# HSI-interface-1.net
KiCad netlist of a schematic drawn in EAGLE
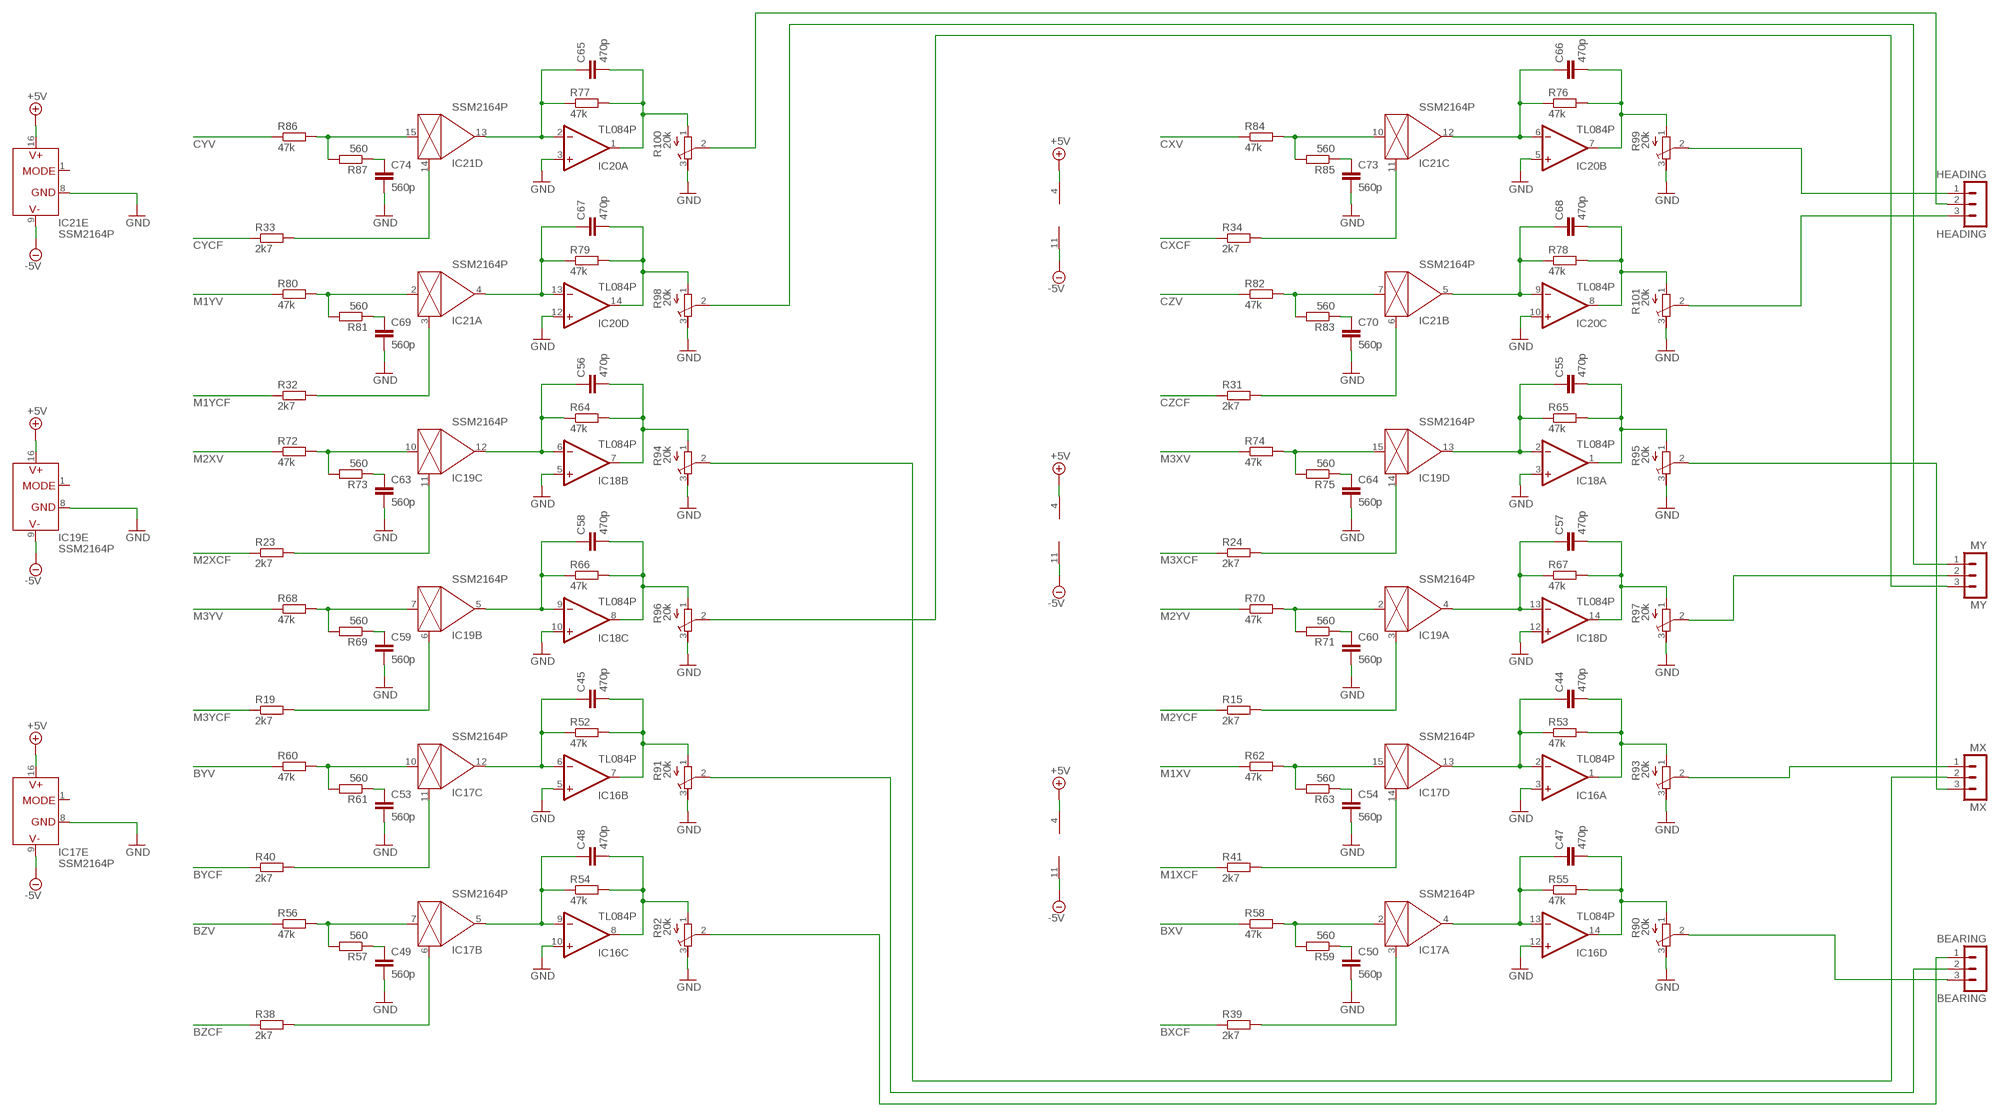
[diagram p0: schematic, sheet 1]
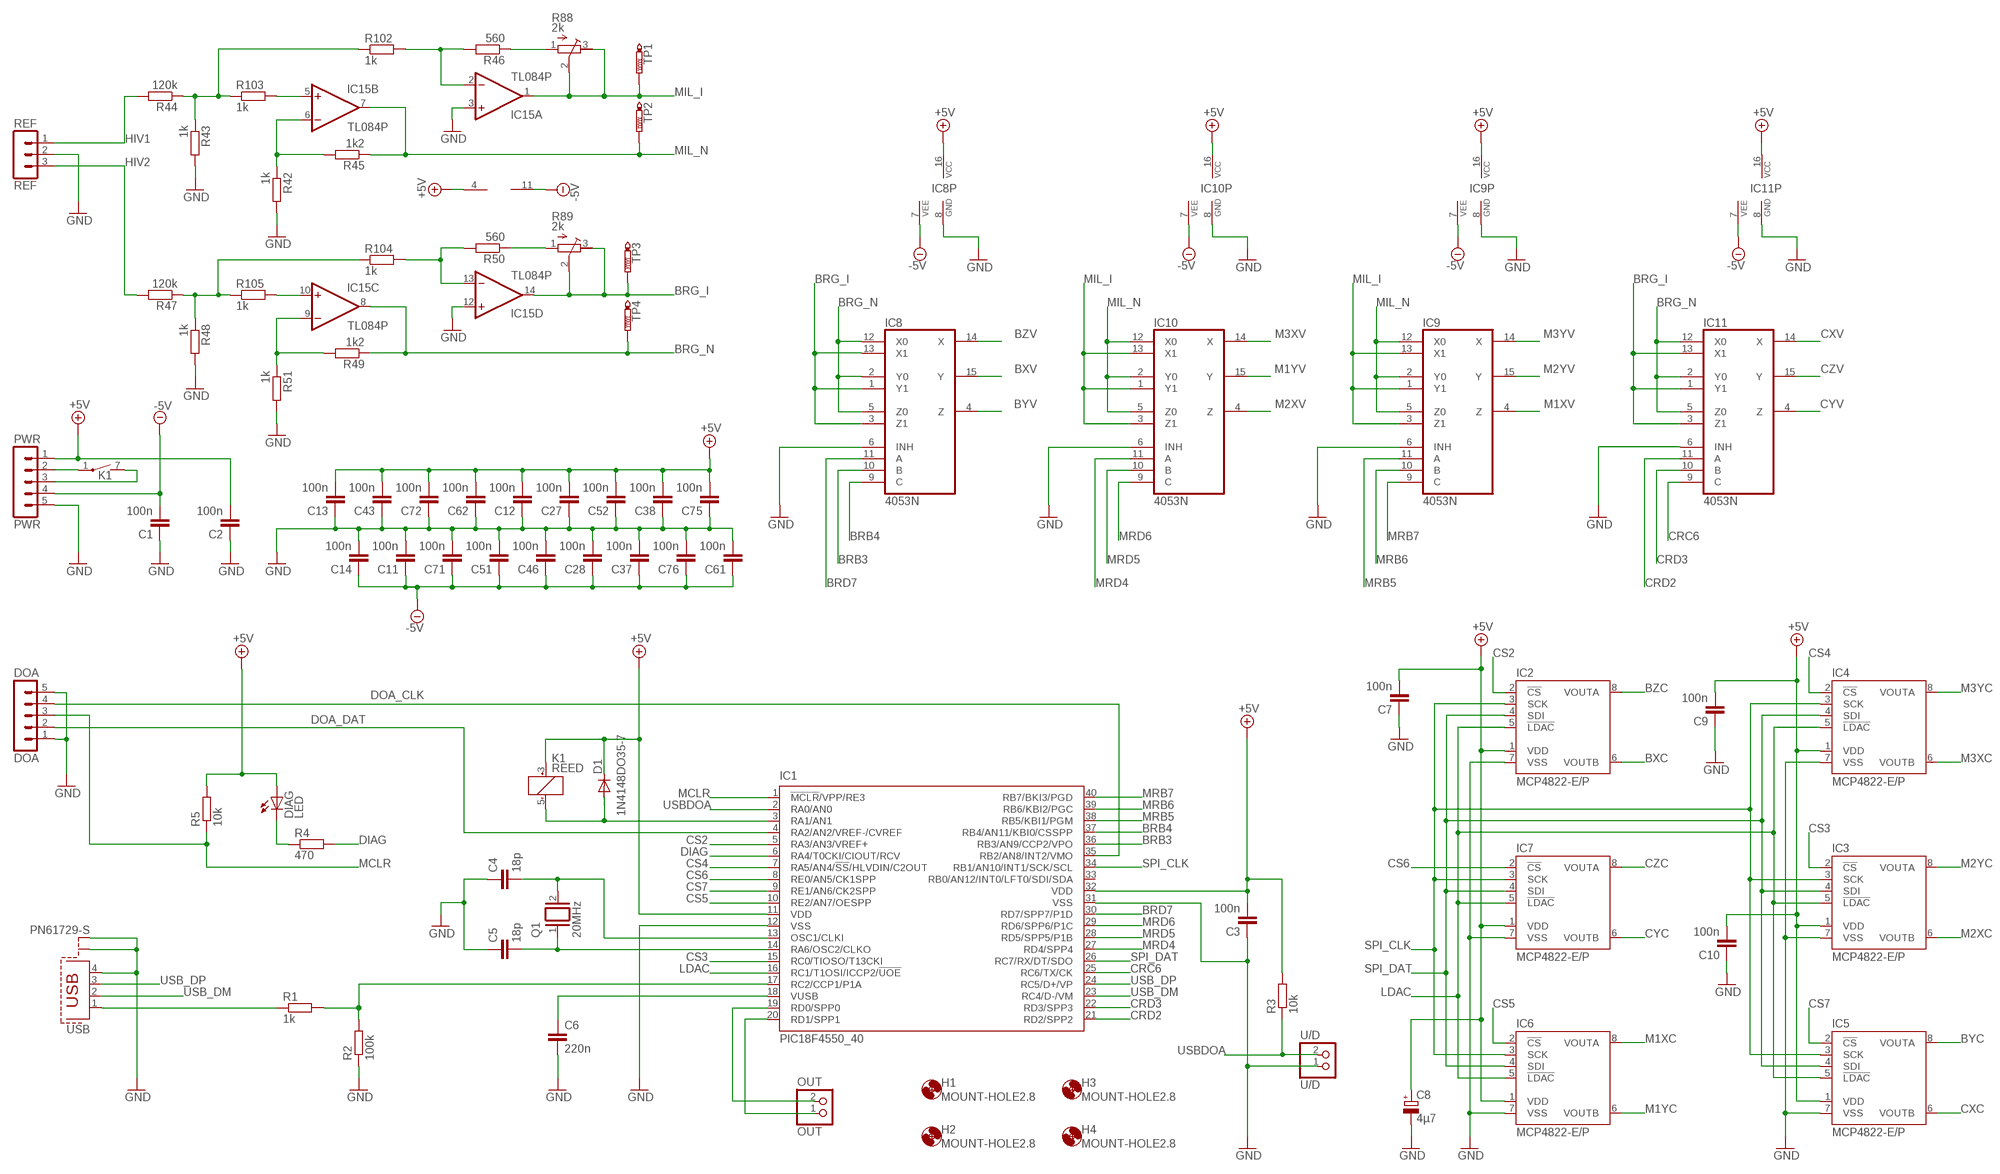
[diagram p1: schematic, sheet 2]
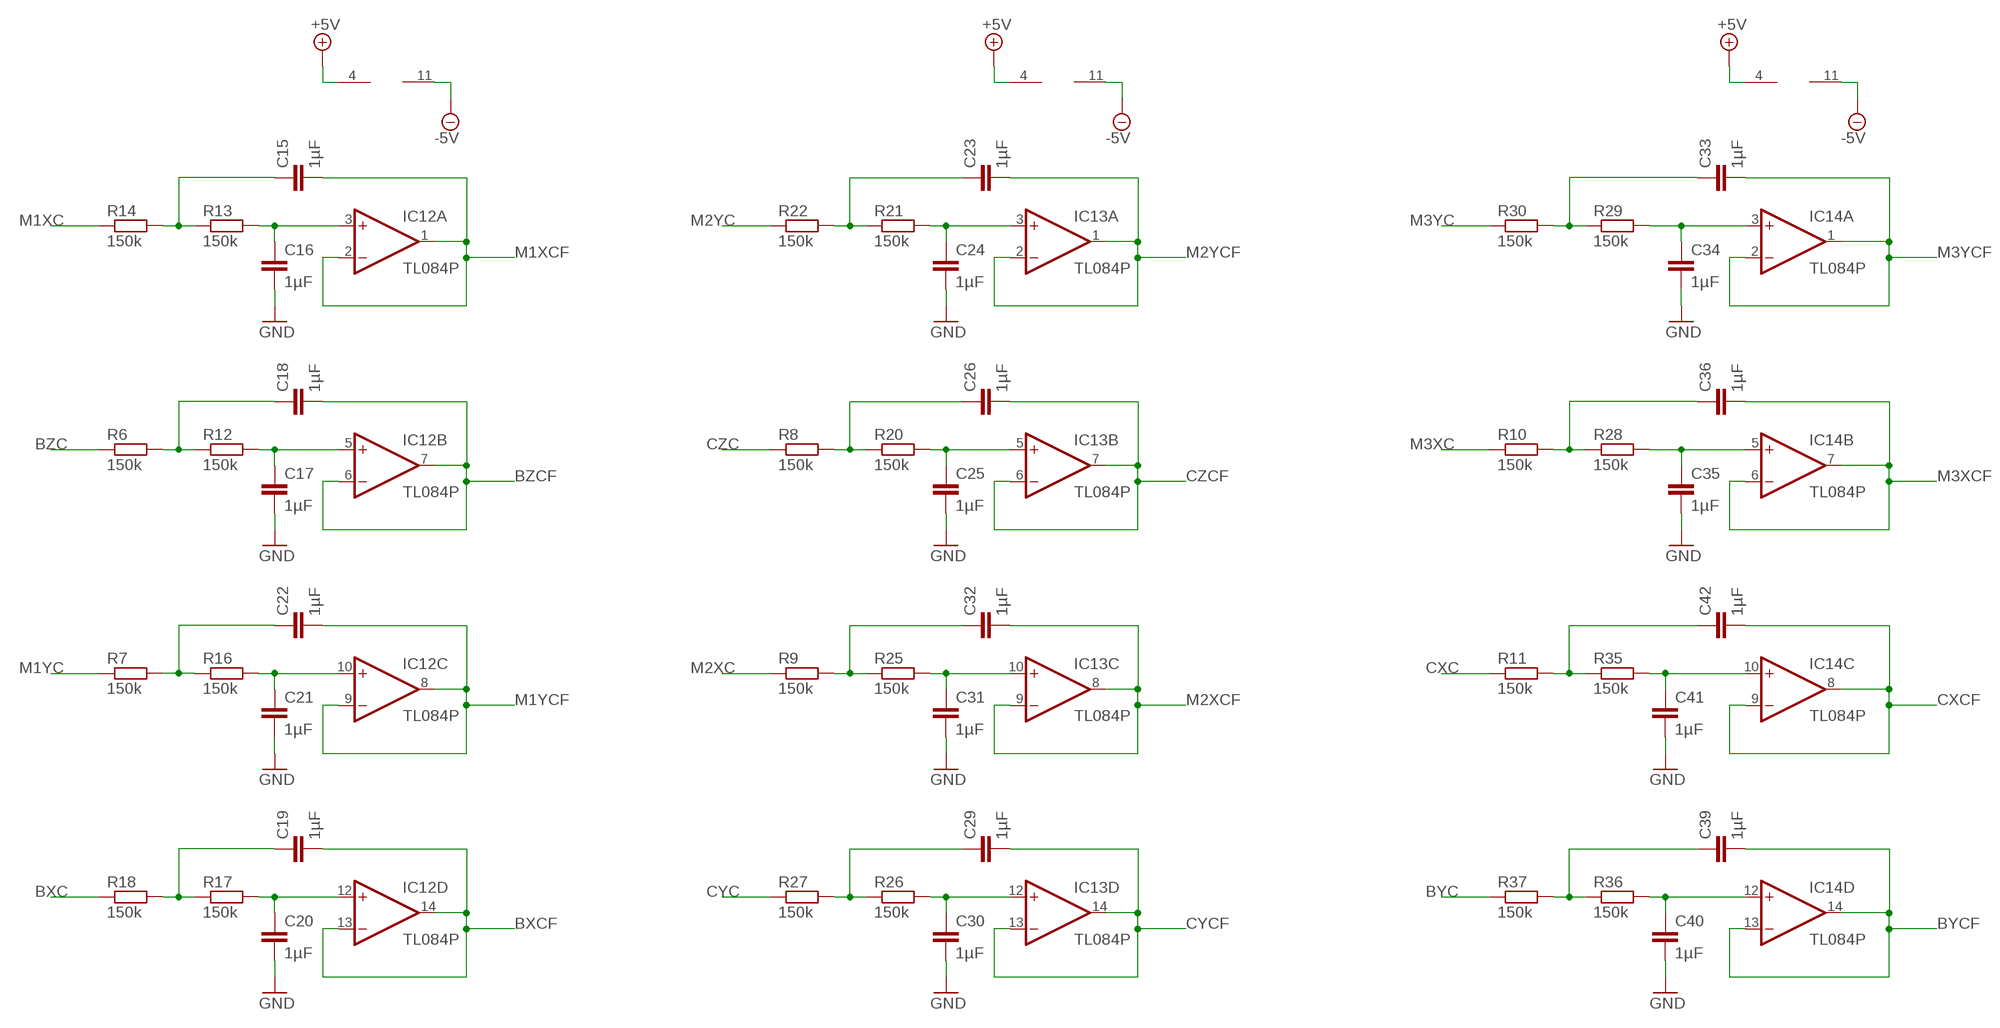
[diagram p2: schematic, sheet 3]

(export (version "E")
  (design (tool "Eeschema 10.0.6"))
  (components
    (comp (ref "C15")
      (value "1µF")
      (footprint "eagle-import:C025-025X050")
      (libsource (lib "eagle-import") (part "C-EU025-025X050"))
    )
    (comp (ref "C16")
      (value "1µF")
      (footprint "eagle-import:C025-025X050")
      (libsource (lib "eagle-import") (part "C-EU025-025X050"))
    )
    (comp (ref "C17")
      (value "1µF")
      (footprint "eagle-import:C025-025X050")
      (libsource (lib "eagle-import") (part "C-EU025-025X050"))
    )
    (comp (ref "C18")
      (value "1µF")
      (footprint "eagle-import:C025-025X050")
      (libsource (lib "eagle-import") (part "C-EU025-025X050"))
    )
    (comp (ref "C19")
      (value "1µF")
      (footprint "eagle-import:C025-025X050")
      (libsource (lib "eagle-import") (part "C-EU025-025X050"))
    )
    (comp (ref "C20")
      (value "1µF")
      (footprint "eagle-import:C025-025X050")
      (libsource (lib "eagle-import") (part "C-EU025-025X050"))
    )
    (comp (ref "C21")
      (value "1µF")
      (footprint "eagle-import:C025-025X050")
      (libsource (lib "eagle-import") (part "C-EU025-025X050"))
    )
    (comp (ref "C22")
      (value "1µF")
      (footprint "eagle-import:C025-025X050")
      (libsource (lib "eagle-import") (part "C-EU025-025X050"))
    )
    (comp (ref "C23")
      (value "1µF")
      (footprint "eagle-import:C025-025X050")
      (libsource (lib "eagle-import") (part "C-EU025-025X050"))
    )
    (comp (ref "C24")
      (value "1µF")
      (footprint "eagle-import:C025-025X050")
      (libsource (lib "eagle-import") (part "C-EU025-025X050"))
    )
    (comp (ref "C25")
      (value "1µF")
      (footprint "eagle-import:C025-025X050")
      (libsource (lib "eagle-import") (part "C-EU025-025X050"))
    )
    (comp (ref "C26")
      (value "1µF")
      (footprint "eagle-import:C025-025X050")
      (libsource (lib "eagle-import") (part "C-EU025-025X050"))
    )
    (comp (ref "C29")
      (value "1µF")
      (footprint "eagle-import:C025-025X050")
      (libsource (lib "eagle-import") (part "C-EU025-025X050"))
    )
    (comp (ref "C30")
      (value "1µF")
      (footprint "eagle-import:C025-025X050")
      (libsource (lib "eagle-import") (part "C-EU025-025X050"))
    )
    (comp (ref "C31")
      (value "1µF")
      (footprint "eagle-import:C025-025X050")
      (libsource (lib "eagle-import") (part "C-EU025-025X050"))
    )
    (comp (ref "C32")
      (value "1µF")
      (footprint "eagle-import:C025-025X050")
      (libsource (lib "eagle-import") (part "C-EU025-025X050"))
    )
    (comp (ref "C33")
      (value "1µF")
      (footprint "eagle-import:C025-025X050")
      (libsource (lib "eagle-import") (part "C-EU025-025X050"))
    )
    (comp (ref "C34")
      (value "1µF")
      (footprint "eagle-import:C025-025X050")
      (libsource (lib "eagle-import") (part "C-EU025-025X050"))
    )
    (comp (ref "C35")
      (value "1µF")
      (footprint "eagle-import:C025-025X050")
      (libsource (lib "eagle-import") (part "C-EU025-025X050"))
    )
    (comp (ref "C36")
      (value "1µF")
      (footprint "eagle-import:C025-025X050")
      (libsource (lib "eagle-import") (part "C-EU025-025X050"))
    )
    (comp (ref "C39")
      (value "1µF")
      (footprint "eagle-import:C025-025X050")
      (libsource (lib "eagle-import") (part "C-EU025-025X050"))
    )
    (comp (ref "C40")
      (value "1µF")
      (footprint "eagle-import:C025-025X050")
      (libsource (lib "eagle-import") (part "C-EU025-025X050"))
    )
    (comp (ref "C41")
      (value "1µF")
      (footprint "eagle-import:C025-025X050")
      (libsource (lib "eagle-import") (part "C-EU025-025X050"))
    )
    (comp (ref "C42")
      (value "1µF")
      (footprint "eagle-import:C025-025X050")
      (libsource (lib "eagle-import") (part "C-EU025-025X050"))
    )
    (comp (ref "IC12")
      (value "TL084P")
      (footprint "eagle-import:DIL14")
      (libsource (lib "eagle-import") (part "TL084P"))
    )
    (comp (ref "IC13")
      (value "TL084P")
      (footprint "eagle-import:DIL14")
      (libsource (lib "eagle-import") (part "TL084P"))
    )
    (comp (ref "IC14")
      (value "TL084P")
      (footprint "eagle-import:DIL14")
      (libsource (lib "eagle-import") (part "TL084P"))
    )
    (comp (ref "R6")
      (value "150k")
      (footprint "eagle-import:0207_7")
      (libsource (lib "eagle-import") (part "R-EU_0207/7"))
    )
    (comp (ref "R7")
      (value "150k")
      (footprint "eagle-import:0207_7")
      (libsource (lib "eagle-import") (part "R-EU_0207/7"))
    )
    (comp (ref "R8")
      (value "150k")
      (footprint "eagle-import:0207_7")
      (libsource (lib "eagle-import") (part "R-EU_0207/7"))
    )
    (comp (ref "R9")
      (value "150k")
      (footprint "eagle-import:0207_7")
      (libsource (lib "eagle-import") (part "R-EU_0207/7"))
    )
    (comp (ref "R10")
      (value "150k")
      (footprint "eagle-import:0207_7")
      (libsource (lib "eagle-import") (part "R-EU_0207/7"))
    )
    (comp (ref "R11")
      (value "150k")
      (footprint "eagle-import:0207_7")
      (libsource (lib "eagle-import") (part "R-EU_0207/7"))
    )
    (comp (ref "R12")
      (value "150k")
      (footprint "eagle-import:0207_7")
      (libsource (lib "eagle-import") (part "R-EU_0207/7"))
    )
    (comp (ref "R13")
      (value "150k")
      (footprint "eagle-import:0207_7")
      (libsource (lib "eagle-import") (part "R-EU_0207/7"))
    )
    (comp (ref "R14")
      (value "150k")
      (footprint "eagle-import:0207_7")
      (libsource (lib "eagle-import") (part "R-EU_0207/7"))
    )
    (comp (ref "R16")
      (value "150k")
      (footprint "eagle-import:0207_7")
      (libsource (lib "eagle-import") (part "R-EU_0207/7"))
    )
    (comp (ref "R17")
      (value "150k")
      (footprint "eagle-import:0207_7")
      (libsource (lib "eagle-import") (part "R-EU_0207/7"))
    )
    (comp (ref "R18")
      (value "150k")
      (footprint "eagle-import:0207_7")
      (libsource (lib "eagle-import") (part "R-EU_0207/7"))
    )
    (comp (ref "R20")
      (value "150k")
      (footprint "eagle-import:0207_7")
      (libsource (lib "eagle-import") (part "R-EU_0207/7"))
    )
    (comp (ref "R21")
      (value "150k")
      (footprint "eagle-import:0207_7")
      (libsource (lib "eagle-import") (part "R-EU_0207/7"))
    )
    (comp (ref "R22")
      (value "150k")
      (footprint "eagle-import:0207_7")
      (libsource (lib "eagle-import") (part "R-EU_0207/7"))
    )
    (comp (ref "R25")
      (value "150k")
      (footprint "eagle-import:0207_7")
      (libsource (lib "eagle-import") (part "R-EU_0207/7"))
    )
    (comp (ref "R26")
      (value "150k")
      (footprint "eagle-import:0207_7")
      (libsource (lib "eagle-import") (part "R-EU_0207/7"))
    )
    (comp (ref "R27")
      (value "150k")
      (footprint "eagle-import:0207_7")
      (libsource (lib "eagle-import") (part "R-EU_0207/7"))
    )
    (comp (ref "R28")
      (value "150k")
      (footprint "eagle-import:0207_7")
      (libsource (lib "eagle-import") (part "R-EU_0207/7"))
    )
    (comp (ref "R29")
      (value "150k")
      (footprint "eagle-import:0207_7")
      (libsource (lib "eagle-import") (part "R-EU_0207/7"))
    )
    (comp (ref "R30")
      (value "150k")
      (footprint "eagle-import:0207_7")
      (libsource (lib "eagle-import") (part "R-EU_0207/7"))
    )
    (comp (ref "R35")
      (value "150k")
      (footprint "eagle-import:0207_7")
      (libsource (lib "eagle-import") (part "R-EU_0207/7"))
    )
    (comp (ref "R36")
      (value "150k")
      (footprint "eagle-import:0207_7")
      (libsource (lib "eagle-import") (part "R-EU_0207/7"))
    )
    (comp (ref "R37")
      (value "150k")
      (footprint "eagle-import:0207_7")
      (libsource (lib "eagle-import") (part "R-EU_0207/7"))
    )
    (comp (ref "C1")
      (value "100n")
      (footprint "eagle-import:C025-025X050")
      (libsource (lib "eagle-import") (part "C-EU025-025X050"))
    )
    (comp (ref "C2")
      (value "100n")
      (footprint "eagle-import:C025-025X050")
      (libsource (lib "eagle-import") (part "C-EU025-025X050"))
    )
    (comp (ref "C3")
      (value "100n")
      (footprint "eagle-import:C025-025X050")
      (libsource (lib "eagle-import") (part "C-EU025-025X050"))
    )
    (comp (ref "C4")
      (value "18p")
      (footprint "eagle-import:C025-025X050")
      (libsource (lib "eagle-import") (part "C-EU025-025X050"))
    )
    (comp (ref "C5")
      (value "18p")
      (footprint "eagle-import:C025-025X050")
      (libsource (lib "eagle-import") (part "C-EU025-025X050"))
    )
    (comp (ref "C6")
      (value "220n")
      (footprint "eagle-import:C5B3")
      (libsource (lib "eagle-import") (part "C5/3"))
    )
    (comp (ref "C7")
      (value "100n")
      (footprint "eagle-import:C025-025X050")
      (libsource (lib "eagle-import") (part "C-EU025-025X050"))
    )
    (comp (ref "C8")
      (value "4µ7")
      (footprint "eagle-import:E2,5-5")
      (libsource (lib "eagle-import") (part "CPOL-EUE2.5-5"))
    )
    (comp (ref "C9")
      (value "100n")
      (footprint "eagle-import:C025-025X050")
      (libsource (lib "eagle-import") (part "C-EU025-025X050"))
    )
    (comp (ref "C10")
      (value "100n")
      (footprint "eagle-import:C025-025X050")
      (libsource (lib "eagle-import") (part "C-EU025-025X050"))
    )
    (comp (ref "C11")
      (value "100n")
      (footprint "eagle-import:C025-025X050")
      (libsource (lib "eagle-import") (part "C-EU025-025X050"))
    )
    (comp (ref "C12")
      (value "100n")
      (footprint "eagle-import:C025-025X050")
      (libsource (lib "eagle-import") (part "C-EU025-025X050"))
    )
    (comp (ref "C13")
      (value "100n")
      (footprint "eagle-import:C025-025X050")
      (libsource (lib "eagle-import") (part "C-EU025-025X050"))
    )
    (comp (ref "C14")
      (value "100n")
      (footprint "eagle-import:C025-025X050")
      (libsource (lib "eagle-import") (part "C-EU025-025X050"))
    )
    (comp (ref "C27")
      (value "100n")
      (footprint "eagle-import:C025-025X050")
      (libsource (lib "eagle-import") (part "C-EU025-025X050"))
    )
    (comp (ref "C28")
      (value "100n")
      (footprint "eagle-import:C025-025X050")
      (libsource (lib "eagle-import") (part "C-EU025-025X050"))
    )
    (comp (ref "C37")
      (value "100n")
      (footprint "eagle-import:C025-025X050")
      (libsource (lib "eagle-import") (part "C-EU025-025X050"))
    )
    (comp (ref "C38")
      (value "100n")
      (footprint "eagle-import:C025-025X050")
      (libsource (lib "eagle-import") (part "C-EU025-025X050"))
    )
    (comp (ref "C43")
      (value "100n")
      (footprint "eagle-import:C025-025X050")
      (libsource (lib "eagle-import") (part "C-EU025-025X050"))
    )
    (comp (ref "C46")
      (value "100n")
      (footprint "eagle-import:C025-025X050")
      (libsource (lib "eagle-import") (part "C-EU025-025X050"))
    )
    (comp (ref "C51")
      (value "100n")
      (footprint "eagle-import:C025-025X050")
      (libsource (lib "eagle-import") (part "C-EU025-025X050"))
    )
    (comp (ref "C52")
      (value "100n")
      (footprint "eagle-import:C025-025X050")
      (libsource (lib "eagle-import") (part "C-EU025-025X050"))
    )
    (comp (ref "C61")
      (value "100n")
      (footprint "eagle-import:C025-025X050")
      (libsource (lib "eagle-import") (part "C-EU025-025X050"))
    )
    (comp (ref "C62")
      (value "100n")
      (footprint "eagle-import:C025-025X050")
      (libsource (lib "eagle-import") (part "C-EU025-025X050"))
    )
    (comp (ref "C71")
      (value "100n")
      (footprint "eagle-import:C025-025X050")
      (libsource (lib "eagle-import") (part "C-EU025-025X050"))
    )
    (comp (ref "C72")
      (value "100n")
      (footprint "eagle-import:C025-025X050")
      (libsource (lib "eagle-import") (part "C-EU025-025X050"))
    )
    (comp (ref "C75")
      (value "100n")
      (footprint "eagle-import:C025-025X050")
      (libsource (lib "eagle-import") (part "C-EU025-025X050"))
    )
    (comp (ref "C76")
      (value "100n")
      (footprint "eagle-import:C025-025X050")
      (libsource (lib "eagle-import") (part "C-EU025-025X050"))
    )
    (comp (ref "D1")
      (value "1N4148DO35-7")
      (footprint "eagle-import:DO35-7")
      (libsource (lib "eagle-import") (part "1N4148DO35-7"))
    )
    (comp (ref "DIAG")
      (value "LED")
      (footprint "eagle-import:LED3MM")
      (libsource (lib "eagle-import") (part "LED3MM"))
    )
    (comp (ref "DOA")
      (value "DOA")
      (footprint "eagle-import:MA05-1")
      (libsource (lib "eagle-import") (part "MA05-1"))
    )
    (comp (ref "H1")
      (value "MOUNT-HOLE2.8")
      (footprint "eagle-import:2,8")
      (libsource (lib "eagle-import") (part "MOUNT-HOLE2.8"))
    )
    (comp (ref "H2")
      (value "MOUNT-HOLE2.8")
      (footprint "eagle-import:2,8")
      (libsource (lib "eagle-import") (part "MOUNT-HOLE2.8"))
    )
    (comp (ref "H3")
      (value "MOUNT-HOLE2.8")
      (footprint "eagle-import:2,8")
      (libsource (lib "eagle-import") (part "MOUNT-HOLE2.8"))
    )
    (comp (ref "H4")
      (value "MOUNT-HOLE2.8")
      (footprint "eagle-import:2,8")
      (libsource (lib "eagle-import") (part "MOUNT-HOLE2.8"))
    )
    (comp (ref "IC1")
      (value "PIC18F4550_40")
      (footprint "eagle-import:DIL40")
      (fields (field (name "MF") "MICROCHIP") (field (name "MPN") "PIC18F4550-I/P"))
      (libsource (lib "eagle-import") (part "PIC18F4_40550"))
    )
    (comp (ref "IC2")
      (value "MCP4822-E/P")
      (footprint "eagle-import:DIL08")
      (libsource (lib "eagle-import") (part "MCP4822-E/P"))
    )
    (comp (ref "IC3")
      (value "MCP4822-E/P")
      (footprint "eagle-import:DIL08")
      (libsource (lib "eagle-import") (part "MCP4822-E/P"))
    )
    (comp (ref "IC4")
      (value "MCP4822-E/P")
      (footprint "eagle-import:DIL08")
      (libsource (lib "eagle-import") (part "MCP4822-E/P"))
    )
    (comp (ref "IC5")
      (value "MCP4822-E/P")
      (footprint "eagle-import:DIL08")
      (libsource (lib "eagle-import") (part "MCP4822-E/P"))
    )
    (comp (ref "IC6")
      (value "MCP4822-E/P")
      (footprint "eagle-import:DIL08")
      (libsource (lib "eagle-import") (part "MCP4822-E/P"))
    )
    (comp (ref "IC7")
      (value "MCP4822-E/P")
      (footprint "eagle-import:DIL08")
      (libsource (lib "eagle-import") (part "MCP4822-E/P"))
    )
    (comp (ref "IC8")
      (value "4053N")
      (footprint "eagle-import:DIL16")
      (libsource (lib "eagle-import") (part "4053N"))
    )
    (comp (ref "IC9")
      (value "4053N")
      (footprint "eagle-import:DIL16")
      (libsource (lib "eagle-import") (part "4053N"))
    )
    (comp (ref "IC10")
      (value "4053N")
      (footprint "eagle-import:DIL16")
      (libsource (lib "eagle-import") (part "4053N"))
    )
    (comp (ref "IC11")
      (value "4053N")
      (footprint "eagle-import:DIL16")
      (libsource (lib "eagle-import") (part "4053N"))
    )
    (comp (ref "IC15")
      (value "TL084P")
      (footprint "eagle-import:DIL14")
      (libsource (lib "eagle-import") (part "TL084P"))
    )
    (comp (ref "K1")
      (value "REED")
      (footprint "eagle-import:REED")
      (libsource (lib "eagle-import") (part "REED"))
    )
    (comp (ref "OUT")
      (value "OUT")
      (footprint "eagle-import:1X02")
      (libsource (lib "eagle-import") (part "PINHD-1X2"))
    )
    (comp (ref "PWR")
      (value "PWR")
      (footprint "eagle-import:MA05-1")
      (libsource (lib "eagle-import") (part "MA05-1"))
    )
    (comp (ref "Q1")
      (value "20MHz")
      (footprint "eagle-import:QS")
      (libsource (lib "eagle-import") (part "XTAL/S"))
    )
    (comp (ref "R1")
      (value "1k")
      (footprint "eagle-import:0204_7")
      (libsource (lib "eagle-import") (part "R-EU_0204/7"))
    )
    (comp (ref "R2")
      (value "100k")
      (footprint "eagle-import:0204_7")
      (libsource (lib "eagle-import") (part "R-EU_0204/7"))
    )
    (comp (ref "R3")
      (value "10k")
      (footprint "eagle-import:0204_7")
      (libsource (lib "eagle-import") (part "R-EU_0204/7"))
    )
    (comp (ref "R4")
      (value "470")
      (footprint "eagle-import:0204_7")
      (libsource (lib "eagle-import") (part "R-EU_0204/7"))
    )
    (comp (ref "R5")
      (value "10k")
      (footprint "eagle-import:0204_7")
      (libsource (lib "eagle-import") (part "R-EU_0204/7"))
    )
    (comp (ref "R42")
      (value "1k")
      (footprint "eagle-import:0204_7")
      (libsource (lib "eagle-import") (part "R-EU_0204/7"))
    )
    (comp (ref "R43")
      (value "1k")
      (footprint "eagle-import:0204_7")
      (libsource (lib "eagle-import") (part "R-EU_0204/7"))
    )
    (comp (ref "R44")
      (value "120k")
      (footprint "eagle-import:0204_7")
      (libsource (lib "eagle-import") (part "R-EU_0204/7"))
    )
    (comp (ref "R45")
      (value "1k2")
      (footprint "eagle-import:0204_7")
      (libsource (lib "eagle-import") (part "R-EU_0204/7"))
    )
    (comp (ref "R46")
      (value "560")
      (footprint "eagle-import:0204_7")
      (libsource (lib "eagle-import") (part "R-EU_0204/7"))
    )
    (comp (ref "R47")
      (value "120k")
      (footprint "eagle-import:0204_7")
      (libsource (lib "eagle-import") (part "R-EU_0204/7"))
    )
    (comp (ref "R48")
      (value "1k")
      (footprint "eagle-import:0204_7")
      (libsource (lib "eagle-import") (part "R-EU_0204/7"))
    )
    (comp (ref "R49")
      (value "1k2")
      (footprint "eagle-import:0204_7")
      (libsource (lib "eagle-import") (part "R-EU_0204/7"))
    )
    (comp (ref "R50")
      (value "560")
      (footprint "eagle-import:0204_7")
      (libsource (lib "eagle-import") (part "R-EU_0204/7"))
    )
    (comp (ref "R51")
      (value "1k")
      (footprint "eagle-import:0204_7")
      (libsource (lib "eagle-import") (part "R-EU_0204/7"))
    )
    (comp (ref "R88")
      (value "2k")
      (footprint "eagle-import:RTRIM64Z")
      (libsource (lib "eagle-import") (part "R-TRIMM64Z"))
    )
    (comp (ref "R89")
      (value "2k")
      (footprint "eagle-import:RTRIM64Z")
      (libsource (lib "eagle-import") (part "R-TRIMM64Z"))
    )
    (comp (ref "R102")
      (value "1k")
      (footprint "eagle-import:0204_7")
      (libsource (lib "eagle-import") (part "R-EU_0204/7"))
    )
    (comp (ref "R103")
      (value "1k")
      (footprint "eagle-import:0204_7")
      (libsource (lib "eagle-import") (part "R-EU_0204/7"))
    )
    (comp (ref "R104")
      (value "1k")
      (footprint "eagle-import:0204_7")
      (libsource (lib "eagle-import") (part "R-EU_0204/7"))
    )
    (comp (ref "R105")
      (value "1k")
      (footprint "eagle-import:0204_7")
      (libsource (lib "eagle-import") (part "R-EU_0204/7"))
    )
    (comp (ref "REF")
      (value "REF")
      (footprint "eagle-import:MA03-1")
      (libsource (lib "eagle-import") (part "MA03-1"))
    )
    (comp (ref "TP1")
      (value "PTR1PAD1-13")
      (footprint "eagle-import:P1-13")
      (libsource (lib "eagle-import") (part "PTR1PAD1-13"))
    )
    (comp (ref "TP2")
      (value "PTR1PAD1-13")
      (footprint "eagle-import:P1-13")
      (libsource (lib "eagle-import") (part "PTR1PAD1-13"))
    )
    (comp (ref "TP3")
      (value "PTR1PAD1-13")
      (footprint "eagle-import:P1-13")
      (libsource (lib "eagle-import") (part "PTR1PAD1-13"))
    )
    (comp (ref "TP4")
      (value "PTR1PAD1-13")
      (footprint "eagle-import:P1-13")
      (libsource (lib "eagle-import") (part "PTR1PAD1-13"))
    )
    (comp (ref "U/D")
      (value "U/D")
      (footprint "eagle-import:1X02")
      (libsource (lib "eagle-import") (part "PINHD-1X2"))
    )
    (comp (ref "USB")
      (value "PN61729-S")
      (footprint "eagle-import:PN61729-S")
      (libsource (lib "eagle-import") (part "PN61729-S"))
    )
    (comp (ref "BEARING")
      (value "BEARING")
      (footprint "eagle-import:MA03-1")
      (libsource (lib "eagle-import") (part "MA03-1"))
    )
    (comp (ref "C44")
      (value "470p")
      (footprint "eagle-import:C025-025X050")
      (libsource (lib "eagle-import") (part "C-EU025-025X050"))
    )
    (comp (ref "C45")
      (value "470p")
      (footprint "eagle-import:C025-025X050")
      (libsource (lib "eagle-import") (part "C-EU025-025X050"))
    )
    (comp (ref "C47")
      (value "470p")
      (footprint "eagle-import:C025-025X050")
      (libsource (lib "eagle-import") (part "C-EU025-025X050"))
    )
    (comp (ref "C48")
      (value "470p")
      (footprint "eagle-import:C025-025X050")
      (libsource (lib "eagle-import") (part "C-EU025-025X050"))
    )
    (comp (ref "C49")
      (value "560p")
      (footprint "eagle-import:C025-025X050")
      (libsource (lib "eagle-import") (part "C-EU025-025X050"))
    )
    (comp (ref "C50")
      (value "560p")
      (footprint "eagle-import:C025-025X050")
      (libsource (lib "eagle-import") (part "C-EU025-025X050"))
    )
    (comp (ref "C53")
      (value "560p")
      (footprint "eagle-import:C025-025X050")
      (libsource (lib "eagle-import") (part "C-EU025-025X050"))
    )
    (comp (ref "C54")
      (value "560p")
      (footprint "eagle-import:C025-025X050")
      (libsource (lib "eagle-import") (part "C-EU025-025X050"))
    )
    (comp (ref "C55")
      (value "470p")
      (footprint "eagle-import:C025-025X050")
      (libsource (lib "eagle-import") (part "C-EU025-025X050"))
    )
    (comp (ref "C56")
      (value "470p")
      (footprint "eagle-import:C025-025X050")
      (libsource (lib "eagle-import") (part "C-EU025-025X050"))
    )
    (comp (ref "C57")
      (value "470p")
      (footprint "eagle-import:C025-025X050")
      (libsource (lib "eagle-import") (part "C-EU025-025X050"))
    )
    (comp (ref "C58")
      (value "470p")
      (footprint "eagle-import:C025-025X050")
      (libsource (lib "eagle-import") (part "C-EU025-025X050"))
    )
    (comp (ref "C59")
      (value "560p")
      (footprint "eagle-import:C025-025X050")
      (libsource (lib "eagle-import") (part "C-EU025-025X050"))
    )
    (comp (ref "C60")
      (value "560p")
      (footprint "eagle-import:C025-025X050")
      (libsource (lib "eagle-import") (part "C-EU025-025X050"))
    )
    (comp (ref "C63")
      (value "560p")
      (footprint "eagle-import:C025-025X050")
      (libsource (lib "eagle-import") (part "C-EU025-025X050"))
    )
    (comp (ref "C64")
      (value "560p")
      (footprint "eagle-import:C025-025X050")
      (libsource (lib "eagle-import") (part "C-EU025-025X050"))
    )
    (comp (ref "C65")
      (value "470p")
      (footprint "eagle-import:C025-025X050")
      (libsource (lib "eagle-import") (part "C-EU025-025X050"))
    )
    (comp (ref "C66")
      (value "470p")
      (footprint "eagle-import:C025-025X050")
      (libsource (lib "eagle-import") (part "C-EU025-025X050"))
    )
    (comp (ref "C67")
      (value "470p")
      (footprint "eagle-import:C025-025X050")
      (libsource (lib "eagle-import") (part "C-EU025-025X050"))
    )
    (comp (ref "C68")
      (value "470p")
      (footprint "eagle-import:C025-025X050")
      (libsource (lib "eagle-import") (part "C-EU025-025X050"))
    )
    (comp (ref "C69")
      (value "560p")
      (footprint "eagle-import:C025-025X050")
      (libsource (lib "eagle-import") (part "C-EU025-025X050"))
    )
    (comp (ref "C70")
      (value "560p")
      (footprint "eagle-import:C025-025X050")
      (libsource (lib "eagle-import") (part "C-EU025-025X050"))
    )
    (comp (ref "C73")
      (value "560p")
      (footprint "eagle-import:C025-025X050")
      (libsource (lib "eagle-import") (part "C-EU025-025X050"))
    )
    (comp (ref "C74")
      (value "560p")
      (footprint "eagle-import:C025-025X050")
      (libsource (lib "eagle-import") (part "C-EU025-025X050"))
    )
    (comp (ref "HEADING")
      (value "HEADING")
      (footprint "eagle-import:MA03-1")
      (libsource (lib "eagle-import") (part "MA03-1"))
    )
    (comp (ref "IC16")
      (value "TL084P")
      (footprint "eagle-import:DIL14")
      (libsource (lib "eagle-import") (part "TL084P"))
    )
    (comp (ref "IC17")
      (value "SSM2164P")
      (footprint "eagle-import:DIL16")
      (libsource (lib "eagle-import") (part "SSM2164P"))
    )
    (comp (ref "IC18")
      (value "TL084P")
      (footprint "eagle-import:DIL14")
      (libsource (lib "eagle-import") (part "TL084P"))
    )
    (comp (ref "IC19")
      (value "SSM2164P")
      (footprint "eagle-import:DIL16")
      (libsource (lib "eagle-import") (part "SSM2164P"))
    )
    (comp (ref "IC20")
      (value "TL084P")
      (footprint "eagle-import:DIL14")
      (libsource (lib "eagle-import") (part "TL084P"))
    )
    (comp (ref "IC21")
      (value "SSM2164P")
      (footprint "eagle-import:DIL16")
      (libsource (lib "eagle-import") (part "SSM2164P"))
    )
    (comp (ref "MX")
      (value "MX")
      (footprint "eagle-import:MA03-1")
      (libsource (lib "eagle-import") (part "MA03-1"))
    )
    (comp (ref "MY")
      (value "MY")
      (footprint "eagle-import:MA03-1")
      (libsource (lib "eagle-import") (part "MA03-1"))
    )
    (comp (ref "R15")
      (value "2k7")
      (footprint "eagle-import:0207_7")
      (libsource (lib "eagle-import") (part "R-EU_0207/7"))
    )
    (comp (ref "R19")
      (value "2k7")
      (footprint "eagle-import:0207_7")
      (libsource (lib "eagle-import") (part "R-EU_0207/7"))
    )
    (comp (ref "R23")
      (value "2k7")
      (footprint "eagle-import:0207_7")
      (libsource (lib "eagle-import") (part "R-EU_0207/7"))
    )
    (comp (ref "R24")
      (value "2k7")
      (footprint "eagle-import:0207_7")
      (libsource (lib "eagle-import") (part "R-EU_0207/7"))
    )
    (comp (ref "R31")
      (value "2k7")
      (footprint "eagle-import:0207_7")
      (libsource (lib "eagle-import") (part "R-EU_0207/7"))
    )
    (comp (ref "R32")
      (value "2k7")
      (footprint "eagle-import:0207_7")
      (libsource (lib "eagle-import") (part "R-EU_0207/7"))
    )
    (comp (ref "R33")
      (value "2k7")
      (footprint "eagle-import:0207_7")
      (libsource (lib "eagle-import") (part "R-EU_0207/7"))
    )
    (comp (ref "R34")
      (value "2k7")
      (footprint "eagle-import:0207_7")
      (libsource (lib "eagle-import") (part "R-EU_0207/7"))
    )
    (comp (ref "R38")
      (value "2k7")
      (footprint "eagle-import:0207_7")
      (libsource (lib "eagle-import") (part "R-EU_0207/7"))
    )
    (comp (ref "R39")
      (value "2k7")
      (footprint "eagle-import:0207_7")
      (libsource (lib "eagle-import") (part "R-EU_0207/7"))
    )
    (comp (ref "R40")
      (value "2k7")
      (footprint "eagle-import:0207_7")
      (libsource (lib "eagle-import") (part "R-EU_0207/7"))
    )
    (comp (ref "R41")
      (value "2k7")
      (footprint "eagle-import:0207_7")
      (libsource (lib "eagle-import") (part "R-EU_0207/7"))
    )
    (comp (ref "R52")
      (value "47k")
      (footprint "eagle-import:0207_7")
      (libsource (lib "eagle-import") (part "R-EU_0207/7"))
    )
    (comp (ref "R53")
      (value "47k")
      (footprint "eagle-import:0207_7")
      (libsource (lib "eagle-import") (part "R-EU_0207/7"))
    )
    (comp (ref "R54")
      (value "47k")
      (footprint "eagle-import:0207_7")
      (libsource (lib "eagle-import") (part "R-EU_0207/7"))
    )
    (comp (ref "R55")
      (value "47k")
      (footprint "eagle-import:0207_7")
      (libsource (lib "eagle-import") (part "R-EU_0207/7"))
    )
    (comp (ref "R56")
      (value "47k")
      (footprint "eagle-import:0207_7")
      (libsource (lib "eagle-import") (part "R-EU_0207/7"))
    )
    (comp (ref "R57")
      (value "560")
      (footprint "eagle-import:0207_7")
      (libsource (lib "eagle-import") (part "R-EU_0207/7"))
    )
    (comp (ref "R58")
      (value "47k")
      (footprint "eagle-import:0207_7")
      (libsource (lib "eagle-import") (part "R-EU_0207/7"))
    )
    (comp (ref "R59")
      (value "560")
      (footprint "eagle-import:0207_7")
      (libsource (lib "eagle-import") (part "R-EU_0207/7"))
    )
    (comp (ref "R60")
      (value "47k")
      (footprint "eagle-import:0207_7")
      (libsource (lib "eagle-import") (part "R-EU_0207/7"))
    )
    (comp (ref "R61")
      (value "560")
      (footprint "eagle-import:0207_7")
      (libsource (lib "eagle-import") (part "R-EU_0207/7"))
    )
    (comp (ref "R62")
      (value "47k")
      (footprint "eagle-import:0207_7")
      (libsource (lib "eagle-import") (part "R-EU_0207/7"))
    )
    (comp (ref "R63")
      (value "560")
      (footprint "eagle-import:0207_7")
      (libsource (lib "eagle-import") (part "R-EU_0207/7"))
    )
    (comp (ref "R64")
      (value "47k")
      (footprint "eagle-import:0207_7")
      (libsource (lib "eagle-import") (part "R-EU_0207/7"))
    )
    (comp (ref "R65")
      (value "47k")
      (footprint "eagle-import:0207_7")
      (libsource (lib "eagle-import") (part "R-EU_0207/7"))
    )
    (comp (ref "R66")
      (value "47k")
      (footprint "eagle-import:0207_7")
      (libsource (lib "eagle-import") (part "R-EU_0207/7"))
    )
    (comp (ref "R67")
      (value "47k")
      (footprint "eagle-import:0207_7")
      (libsource (lib "eagle-import") (part "R-EU_0207/7"))
    )
    (comp (ref "R68")
      (value "47k")
      (footprint "eagle-import:0207_7")
      (libsource (lib "eagle-import") (part "R-EU_0207/7"))
    )
    (comp (ref "R69")
      (value "560")
      (footprint "eagle-import:0207_7")
      (libsource (lib "eagle-import") (part "R-EU_0207/7"))
    )
    (comp (ref "R70")
      (value "47k")
      (footprint "eagle-import:0207_7")
      (libsource (lib "eagle-import") (part "R-EU_0207/7"))
    )
    (comp (ref "R71")
      (value "560")
      (footprint "eagle-import:0207_7")
      (libsource (lib "eagle-import") (part "R-EU_0207/7"))
    )
    (comp (ref "R72")
      (value "47k")
      (footprint "eagle-import:0207_7")
      (libsource (lib "eagle-import") (part "R-EU_0207/7"))
    )
    (comp (ref "R73")
      (value "560")
      (footprint "eagle-import:0207_7")
      (libsource (lib "eagle-import") (part "R-EU_0207/7"))
    )
    (comp (ref "R74")
      (value "47k")
      (footprint "eagle-import:0207_7")
      (libsource (lib "eagle-import") (part "R-EU_0207/7"))
    )
    (comp (ref "R75")
      (value "560")
      (footprint "eagle-import:0207_7")
      (libsource (lib "eagle-import") (part "R-EU_0207/7"))
    )
    (comp (ref "R76")
      (value "47k")
      (footprint "eagle-import:0207_7")
      (libsource (lib "eagle-import") (part "R-EU_0207/7"))
    )
    (comp (ref "R77")
      (value "47k")
      (footprint "eagle-import:0207_7")
      (libsource (lib "eagle-import") (part "R-EU_0207/7"))
    )
    (comp (ref "R78")
      (value "47k")
      (footprint "eagle-import:0207_7")
      (libsource (lib "eagle-import") (part "R-EU_0207/7"))
    )
    (comp (ref "R79")
      (value "47k")
      (footprint "eagle-import:0207_7")
      (libsource (lib "eagle-import") (part "R-EU_0207/7"))
    )
    (comp (ref "R80")
      (value "47k")
      (footprint "eagle-import:0207_7")
      (libsource (lib "eagle-import") (part "R-EU_0207/7"))
    )
    (comp (ref "R81")
      (value "560")
      (footprint "eagle-import:0207_7")
      (libsource (lib "eagle-import") (part "R-EU_0207/7"))
    )
    (comp (ref "R82")
      (value "47k")
      (footprint "eagle-import:0207_7")
      (libsource (lib "eagle-import") (part "R-EU_0207/7"))
    )
    (comp (ref "R83")
      (value "560")
      (footprint "eagle-import:0207_7")
      (libsource (lib "eagle-import") (part "R-EU_0207/7"))
    )
    (comp (ref "R84")
      (value "47k")
      (footprint "eagle-import:0207_7")
      (libsource (lib "eagle-import") (part "R-EU_0207/7"))
    )
    (comp (ref "R85")
      (value "560")
      (footprint "eagle-import:0207_7")
      (libsource (lib "eagle-import") (part "R-EU_0207/7"))
    )
    (comp (ref "R86")
      (value "47k")
      (footprint "eagle-import:0207_7")
      (libsource (lib "eagle-import") (part "R-EU_0207/7"))
    )
    (comp (ref "R87")
      (value "560")
      (footprint "eagle-import:0207_7")
      (libsource (lib "eagle-import") (part "R-EU_0207/7"))
    )
    (comp (ref "R90")
      (value "20k")
      (footprint "eagle-import:RTRIM64Z")
      (libsource (lib "eagle-import") (part "R-TRIMM64Z"))
    )
    (comp (ref "R91")
      (value "20k")
      (footprint "eagle-import:RTRIM64Z")
      (libsource (lib "eagle-import") (part "R-TRIMM64Z"))
    )
    (comp (ref "R92")
      (value "20k")
      (footprint "eagle-import:RTRIM64Z")
      (libsource (lib "eagle-import") (part "R-TRIMM64Z"))
    )
    (comp (ref "R93")
      (value "20k")
      (footprint "eagle-import:RTRIM64Z")
      (libsource (lib "eagle-import") (part "R-TRIMM64Z"))
    )
    (comp (ref "R94")
      (value "20k")
      (footprint "eagle-import:RTRIM64Z")
      (libsource (lib "eagle-import") (part "R-TRIMM64Z"))
    )
    (comp (ref "R95")
      (value "20k")
      (footprint "eagle-import:RTRIM64Z")
      (libsource (lib "eagle-import") (part "R-TRIMM64Z"))
    )
    (comp (ref "R96")
      (value "20k")
      (footprint "eagle-import:RTRIM64Z")
      (libsource (lib "eagle-import") (part "R-TRIMM64Z"))
    )
    (comp (ref "R97")
      (value "20k")
      (footprint "eagle-import:RTRIM64Z")
      (libsource (lib "eagle-import") (part "R-TRIMM64Z"))
    )
    (comp (ref "R98")
      (value "20k")
      (footprint "eagle-import:RTRIM64Z")
      (libsource (lib "eagle-import") (part "R-TRIMM64Z"))
    )
    (comp (ref "R99")
      (value "20k")
      (footprint "eagle-import:RTRIM64Z")
      (libsource (lib "eagle-import") (part "R-TRIMM64Z"))
    )
    (comp (ref "R100")
      (value "20k")
      (footprint "eagle-import:RTRIM64Z")
      (libsource (lib "eagle-import") (part "R-TRIMM64Z"))
    )
    (comp (ref "R101")
      (value "20k")
      (footprint "eagle-import:RTRIM64Z")
      (libsource (lib "eagle-import") (part "R-TRIMM64Z"))
    )
  )
  (nets
    (net (code "1") (name "+5V") (class "Default")
      (node (ref "C10") (pin "2") (pinfunction "2_2") (pintype "passive"))
      (node (ref "C12") (pin "2") (pinfunction "2_2") (pintype "passive"))
      (node (ref "C13") (pin "2") (pinfunction "2_2") (pintype "passive"))
      (node (ref "C2") (pin "2") (pinfunction "2_2") (pintype "passive"))
      (node (ref "C27") (pin "2") (pinfunction "2_2") (pintype "passive"))
      (node (ref "C3") (pin "2") (pinfunction "2_2") (pintype "passive"))
      (node (ref "C38") (pin "2") (pinfunction "2_2") (pintype "passive"))
      (node (ref "C43") (pin "2") (pinfunction "2_2") (pintype "passive"))
      (node (ref "C52") (pin "2") (pinfunction "2_2") (pintype "passive"))
      (node (ref "C62") (pin "2") (pinfunction "2_2") (pintype "passive"))
      (node (ref "C7") (pin "2") (pinfunction "2_2") (pintype "passive"))
      (node (ref "C72") (pin "2") (pinfunction "2_2") (pintype "passive"))
      (node (ref "C75") (pin "2") (pinfunction "2_2") (pintype "passive"))
      (node (ref "C8") (pin "+") (pinfunction "+_+") (pintype "passive"))
      (node (ref "C9") (pin "2") (pinfunction "2_2") (pintype "passive"))
      (node (ref "D1") (pin "C") (pinfunction "C_C") (pintype "passive"))
      (node (ref "DIAG") (pin "A") (pinfunction "A_A") (pintype "passive"))
      (node (ref "IC1") (pin "11") (pinfunction "VDD_11") (pintype "power_in"))
      (node (ref "IC1") (pin "32") (pinfunction "VDD_32") (pintype "power_in"))
      (node (ref "IC10") (pin "16") (pinfunction "VCC_16") (pintype "power_in"))
      (node (ref "IC11") (pin "16") (pinfunction "VCC_16") (pintype "power_in"))
      (node (ref "IC12") (pin "4") (pinfunction "V+_4") (pintype "power_in"))
      (node (ref "IC13") (pin "4") (pinfunction "V+_4") (pintype "power_in"))
      (node (ref "IC14") (pin "4") (pinfunction "V+_4") (pintype "power_in"))
      (node (ref "IC15") (pin "4") (pinfunction "V+_4") (pintype "power_in"))
      (node (ref "IC16") (pin "4") (pinfunction "V+_4") (pintype "power_in"))
      (node (ref "IC17") (pin "16") (pinfunction "V+_16") (pintype "power_in"))
      (node (ref "IC18") (pin "4") (pinfunction "V+_4") (pintype "power_in"))
      (node (ref "IC19") (pin "16") (pinfunction "V+_16") (pintype "power_in"))
      (node (ref "IC2") (pin "1") (pinfunction "VDD_1") (pintype "power_in"))
      (node (ref "IC20") (pin "4") (pinfunction "V+_4") (pintype "power_in"))
      (node (ref "IC21") (pin "16") (pinfunction "V+_16") (pintype "power_in"))
      (node (ref "IC3") (pin "1") (pinfunction "VDD_1") (pintype "power_in"))
      (node (ref "IC4") (pin "1") (pinfunction "VDD_1") (pintype "power_in"))
      (node (ref "IC5") (pin "1") (pinfunction "VDD_1") (pintype "power_in"))
      (node (ref "IC6") (pin "1") (pinfunction "VDD_1") (pintype "power_in"))
      (node (ref "IC7") (pin "1") (pinfunction "VDD_1") (pintype "power_in"))
      (node (ref "IC8") (pin "16") (pinfunction "VCC_16") (pintype "power_in"))
      (node (ref "IC9") (pin "16") (pinfunction "VCC_16") (pintype "power_in"))
      (node (ref "K1") (pin "3") (pinfunction "+_3") (pintype "passive"))
      (node (ref "PWR") (pin "1") (pinfunction "1_1") (pintype "passive"))
      (node (ref "R3") (pin "2") (pinfunction "2_2") (pintype "passive"))
      (node (ref "R5") (pin "2") (pinfunction "2_2") (pintype "passive"))
    )
    (net (code "2") (name "-5V") (class "Default")
      (node (ref "C1") (pin "2") (pinfunction "2_2") (pintype "passive"))
      (node (ref "C11") (pin "1") (pinfunction "1_1") (pintype "passive"))
      (node (ref "C14") (pin "1") (pinfunction "1_1") (pintype "passive"))
      (node (ref "C28") (pin "1") (pinfunction "1_1") (pintype "passive"))
      (node (ref "C37") (pin "1") (pinfunction "1_1") (pintype "passive"))
      (node (ref "C46") (pin "1") (pinfunction "1_1") (pintype "passive"))
      (node (ref "C51") (pin "1") (pinfunction "1_1") (pintype "passive"))
      (node (ref "C61") (pin "1") (pinfunction "1_1") (pintype "passive"))
      (node (ref "C71") (pin "1") (pinfunction "1_1") (pintype "passive"))
      (node (ref "C76") (pin "1") (pinfunction "1_1") (pintype "passive"))
      (node (ref "IC10") (pin "7") (pinfunction "VEE_7") (pintype "power_in"))
      (node (ref "IC11") (pin "7") (pinfunction "VEE_7") (pintype "power_in"))
      (node (ref "IC12") (pin "11") (pinfunction "V-_11") (pintype "power_in"))
      (node (ref "IC13") (pin "11") (pinfunction "V-_11") (pintype "power_in"))
      (node (ref "IC14") (pin "11") (pinfunction "V-_11") (pintype "power_in"))
      (node (ref "IC15") (pin "11") (pinfunction "V-_11") (pintype "power_in"))
      (node (ref "IC16") (pin "11") (pinfunction "V-_11") (pintype "power_in"))
      (node (ref "IC17") (pin "9") (pinfunction "V-_9") (pintype "power_in"))
      (node (ref "IC18") (pin "11") (pinfunction "V-_11") (pintype "power_in"))
      (node (ref "IC19") (pin "9") (pinfunction "V-_9") (pintype "power_in"))
      (node (ref "IC20") (pin "11") (pinfunction "V-_11") (pintype "power_in"))
      (node (ref "IC21") (pin "9") (pinfunction "V-_9") (pintype "power_in"))
      (node (ref "IC8") (pin "7") (pinfunction "VEE_7") (pintype "power_in"))
      (node (ref "IC9") (pin "7") (pinfunction "VEE_7") (pintype "power_in"))
      (node (ref "PWR") (pin "4") (pinfunction "4_4") (pintype "passive"))
    )
    (net (code "3") (name "BRB3") (class "Default")
      (node (ref "IC1") (pin "36") (pinfunction "RB3/AN9/CCP2/VPO_36") (pintype "bidirectional"))
      (node (ref "IC8") (pin "10") (pinfunction "B_10") (pintype "input"))
    )
    (net (code "4") (name "BRB4") (class "Default")
      (node (ref "IC1") (pin "37") (pinfunction "RB4/AN11/KBI0/CSSPP_37") (pintype "bidirectional"))
      (node (ref "IC8") (pin "9") (pinfunction "C_9") (pintype "input"))
    )
    (net (code "5") (name "BRD7") (class "Default")
      (node (ref "IC1") (pin "30") (pinfunction "RD7/SPP7/P1D_30") (pintype "bidirectional"))
      (node (ref "IC8") (pin "11") (pinfunction "A_11") (pintype "input"))
    )
    (net (code "6") (name "BRG_I") (class "Default")
      (node (ref "IC11") (pin "1") (pinfunction "Y1_1") (pintype "bidirectional"))
      (node (ref "IC11") (pin "13") (pinfunction "X1_13") (pintype "bidirectional"))
      (node (ref "IC11") (pin "3") (pinfunction "Z1_3") (pintype "bidirectional"))
      (node (ref "IC15") (pin "14") (pinfunction "OUT_14") (pintype "output"))
      (node (ref "IC8") (pin "1") (pinfunction "Y1_1") (pintype "bidirectional"))
      (node (ref "IC8") (pin "13") (pinfunction "X1_13") (pintype "bidirectional"))
      (node (ref "IC8") (pin "3") (pinfunction "Z1_3") (pintype "bidirectional"))
      (node (ref "R89") (pin "2") (pinfunction "S_2") (pintype "passive"))
      (node (ref "R89") (pin "3") (pinfunction "A_3") (pintype "passive"))
      (node (ref "TP3") (pin "TP") (pinfunction "TP_TP") (pintype "input"))
    )
    (net (code "7") (name "BRG_N") (class "Default")
      (node (ref "IC11") (pin "12") (pinfunction "X0_12") (pintype "bidirectional"))
      (node (ref "IC11") (pin "2") (pinfunction "Y0_2") (pintype "bidirectional"))
      (node (ref "IC11") (pin "5") (pinfunction "Z0_5") (pintype "bidirectional"))
      (node (ref "IC15") (pin "8") (pinfunction "OUT_8") (pintype "output"))
      (node (ref "IC8") (pin "12") (pinfunction "X0_12") (pintype "bidirectional"))
      (node (ref "IC8") (pin "2") (pinfunction "Y0_2") (pintype "bidirectional"))
      (node (ref "IC8") (pin "5") (pinfunction "Z0_5") (pintype "bidirectional"))
      (node (ref "R49") (pin "1") (pinfunction "1_1") (pintype "passive"))
      (node (ref "TP4") (pin "TP") (pinfunction "TP_TP") (pintype "input"))
    )
    (net (code "8") (name "BXC") (class "Default")
      (node (ref "IC2") (pin "6") (pinfunction "VOUTB_6") (pintype "output"))
      (node (ref "R18") (pin "1") (pinfunction "1_1") (pintype "passive"))
    )
    (net (code "9") (name "BXCF") (class "Default")
      (node (ref "C19") (pin "2") (pinfunction "2_2") (pintype "passive"))
      (node (ref "IC12") (pin "13") (pinfunction "-IN_13") (pintype "input"))
      (node (ref "IC12") (pin "14") (pinfunction "OUT_14") (pintype "output"))
      (node (ref "R39") (pin "1") (pinfunction "1_1") (pintype "passive"))
    )
    (net (code "10") (name "BXV") (class "Default")
      (node (ref "IC8") (pin "15") (pinfunction "Y_15") (pintype "bidirectional"))
      (node (ref "R58") (pin "1") (pinfunction "1_1") (pintype "passive"))
    )
    (net (code "11") (name "BYC") (class "Default")
      (node (ref "IC5") (pin "8") (pinfunction "VOUTA_8") (pintype "output"))
      (node (ref "R37") (pin "1") (pinfunction "1_1") (pintype "passive"))
    )
    (net (code "12") (name "BYCF") (class "Default")
      (node (ref "C39") (pin "2") (pinfunction "2_2") (pintype "passive"))
      (node (ref "IC14") (pin "13") (pinfunction "-IN_13") (pintype "input"))
      (node (ref "IC14") (pin "14") (pinfunction "OUT_14") (pintype "output"))
      (node (ref "R40") (pin "1") (pinfunction "1_1") (pintype "passive"))
    )
    (net (code "13") (name "BYV") (class "Default")
      (node (ref "IC8") (pin "4") (pinfunction "Z_4") (pintype "bidirectional"))
      (node (ref "R60") (pin "1") (pinfunction "1_1") (pintype "passive"))
    )
    (net (code "14") (name "BZC") (class "Default")
      (node (ref "IC2") (pin "8") (pinfunction "VOUTA_8") (pintype "output"))
      (node (ref "R6") (pin "1") (pinfunction "1_1") (pintype "passive"))
    )
    (net (code "15") (name "BZCF") (class "Default")
      (node (ref "C18") (pin "2") (pinfunction "2_2") (pintype "passive"))
      (node (ref "IC12") (pin "6") (pinfunction "-IN_6") (pintype "input"))
      (node (ref "IC12") (pin "7") (pinfunction "OUT_7") (pintype "output"))
      (node (ref "R38") (pin "1") (pinfunction "1_1") (pintype "passive"))
    )
    (net (code "16") (name "BZV") (class "Default")
      (node (ref "IC8") (pin "14") (pinfunction "X_14") (pintype "bidirectional"))
      (node (ref "R56") (pin "1") (pinfunction "1_1") (pintype "passive"))
    )
    (net (code "17") (name "CRC6") (class "Default")
      (node (ref "IC1") (pin "25") (pinfunction "RC6/TX/CK_25") (pintype "bidirectional"))
      (node (ref "IC11") (pin "9") (pinfunction "C_9") (pintype "input"))
    )
    (net (code "18") (name "CRD2") (class "Default")
      (node (ref "IC1") (pin "21") (pinfunction "RD2/SPP2_21") (pintype "bidirectional"))
      (node (ref "IC11") (pin "11") (pinfunction "A_11") (pintype "input"))
    )
    (net (code "19") (name "CRD3") (class "Default")
      (node (ref "IC1") (pin "22") (pinfunction "RD3/SPP3_22") (pintype "bidirectional"))
      (node (ref "IC11") (pin "10") (pinfunction "B_10") (pintype "input"))
    )
    (net (code "20") (name "CS2") (class "Default")
      (node (ref "IC1") (pin "5") (pinfunction "RA3/AN3/VREF+_5") (pintype "bidirectional"))
      (node (ref "IC2") (pin "2") (pinfunction "~{CS}_2") (pintype "input"))
    )
    (net (code "21") (name "CS3") (class "Default")
      (node (ref "IC1") (pin "15") (pinfunction "RC0/TIOSO/T13CKI_15") (pintype "bidirectional"))
      (node (ref "IC3") (pin "2") (pinfunction "~{CS}_2") (pintype "input"))
    )
    (net (code "22") (name "CS4") (class "Default")
      (node (ref "IC1") (pin "7") (pinfunction "RA5/AN4/~{SS}/HLVDIN/C2OUT_7") (pintype "bidirectional"))
      (node (ref "IC4") (pin "2") (pinfunction "~{CS}_2") (pintype "input"))
    )
    (net (code "23") (name "CS5") (class "Default")
      (node (ref "IC1") (pin "10") (pinfunction "RE2/AN7/OESPP_10") (pintype "bidirectional"))
      (node (ref "IC6") (pin "2") (pinfunction "~{CS}_2") (pintype "input"))
    )
    (net (code "24") (name "CS6") (class "Default")
      (node (ref "IC1") (pin "8") (pinfunction "RE0/AN5/CK1SPP_8") (pintype "bidirectional"))
      (node (ref "IC7") (pin "2") (pinfunction "~{CS}_2") (pintype "input"))
    )
    (net (code "25") (name "CS7") (class "Default")
      (node (ref "IC1") (pin "9") (pinfunction "RE1/AN6/CK2SPP_9") (pintype "bidirectional"))
      (node (ref "IC5") (pin "2") (pinfunction "~{CS}_2") (pintype "input"))
    )
    (net (code "26") (name "CXC") (class "Default")
      (node (ref "IC5") (pin "6") (pinfunction "VOUTB_6") (pintype "output"))
      (node (ref "R11") (pin "1") (pinfunction "1_1") (pintype "passive"))
    )
    (net (code "27") (name "CXCF") (class "Default")
      (node (ref "C42") (pin "2") (pinfunction "2_2") (pintype "passive"))
      (node (ref "IC14") (pin "8") (pinfunction "OUT_8") (pintype "output"))
      (node (ref "IC14") (pin "9") (pinfunction "-IN_9") (pintype "input"))
      (node (ref "R34") (pin "1") (pinfunction "1_1") (pintype "passive"))
    )
    (net (code "28") (name "CXV") (class "Default")
      (node (ref "IC11") (pin "14") (pinfunction "X_14") (pintype "bidirectional"))
      (node (ref "R84") (pin "1") (pinfunction "1_1") (pintype "passive"))
    )
    (net (code "29") (name "CYC") (class "Default")
      (node (ref "IC7") (pin "6") (pinfunction "VOUTB_6") (pintype "output"))
      (node (ref "R27") (pin "1") (pinfunction "1_1") (pintype "passive"))
    )
    (net (code "30") (name "CYCF") (class "Default")
      (node (ref "C29") (pin "2") (pinfunction "2_2") (pintype "passive"))
      (node (ref "IC13") (pin "13") (pinfunction "-IN_13") (pintype "input"))
      (node (ref "IC13") (pin "14") (pinfunction "OUT_14") (pintype "output"))
      (node (ref "R33") (pin "1") (pinfunction "1_1") (pintype "passive"))
    )
    (net (code "31") (name "CYV") (class "Default")
      (node (ref "IC11") (pin "4") (pinfunction "Z_4") (pintype "bidirectional"))
      (node (ref "R86") (pin "1") (pinfunction "1_1") (pintype "passive"))
    )
    (net (code "32") (name "CZC") (class "Default")
      (node (ref "IC7") (pin "8") (pinfunction "VOUTA_8") (pintype "output"))
      (node (ref "R8") (pin "1") (pinfunction "1_1") (pintype "passive"))
    )
    (net (code "33") (name "CZCF") (class "Default")
      (node (ref "C26") (pin "2") (pinfunction "2_2") (pintype "passive"))
      (node (ref "IC13") (pin "6") (pinfunction "-IN_6") (pintype "input"))
      (node (ref "IC13") (pin "7") (pinfunction "OUT_7") (pintype "output"))
      (node (ref "R31") (pin "1") (pinfunction "1_1") (pintype "passive"))
    )
    (net (code "34") (name "CZV") (class "Default")
      (node (ref "IC11") (pin "15") (pinfunction "Y_15") (pintype "bidirectional"))
      (node (ref "R82") (pin "1") (pinfunction "1_1") (pintype "passive"))
    )
    (net (code "35") (name "DIAG") (class "Default")
      (node (ref "IC1") (pin "6") (pinfunction "RA4/T0CKI/CIOUT/RCV_6") (pintype "bidirectional"))
      (node (ref "R4") (pin "2") (pinfunction "2_2") (pintype "passive"))
    )
    (net (code "36") (name "DOA_CLK") (class "Default")
      (node (ref "DOA") (pin "4") (pinfunction "4_4") (pintype "passive"))
      (node (ref "IC1") (pin "35") (pinfunction "RB2/AN8/INT2/VMO_35") (pintype "bidirectional"))
    )
    (net (code "37") (name "DOA_DAT") (class "Default")
      (node (ref "DOA") (pin "2") (pinfunction "2_2") (pintype "passive"))
      (node (ref "IC1") (pin "4") (pinfunction "RA2/AN2/VREF-/CVREF_4") (pintype "bidirectional"))
    )
    (net (code "38") (name "GND") (class "Default")
      (node (ref "C1") (pin "1") (pinfunction "1_1") (pintype "passive"))
      (node (ref "C10") (pin "1") (pinfunction "1_1") (pintype "passive"))
      (node (ref "C11") (pin "2") (pinfunction "2_2") (pintype "passive"))
      (node (ref "C12") (pin "1") (pinfunction "1_1") (pintype "passive"))
      (node (ref "C13") (pin "1") (pinfunction "1_1") (pintype "passive"))
      (node (ref "C14") (pin "2") (pinfunction "2_2") (pintype "passive"))
      (node (ref "C16") (pin "2") (pinfunction "2_2") (pintype "passive"))
      (node (ref "C17") (pin "2") (pinfunction "2_2") (pintype "passive"))
      (node (ref "C2") (pin "1") (pinfunction "1_1") (pintype "passive"))
      (node (ref "C20") (pin "2") (pinfunction "2_2") (pintype "passive"))
      (node (ref "C21") (pin "2") (pinfunction "2_2") (pintype "passive"))
      (node (ref "C24") (pin "2") (pinfunction "2_2") (pintype "passive"))
      (node (ref "C25") (pin "2") (pinfunction "2_2") (pintype "passive"))
      (node (ref "C27") (pin "1") (pinfunction "1_1") (pintype "passive"))
      (node (ref "C28") (pin "2") (pinfunction "2_2") (pintype "passive"))
      (node (ref "C3") (pin "1") (pinfunction "1_1") (pintype "passive"))
      (node (ref "C30") (pin "2") (pinfunction "2_2") (pintype "passive"))
      (node (ref "C31") (pin "2") (pinfunction "2_2") (pintype "passive"))
      (node (ref "C34") (pin "2") (pinfunction "2_2") (pintype "passive"))
      (node (ref "C35") (pin "2") (pinfunction "2_2") (pintype "passive"))
      (node (ref "C37") (pin "2") (pinfunction "2_2") (pintype "passive"))
      (node (ref "C38") (pin "1") (pinfunction "1_1") (pintype "passive"))
      (node (ref "C4") (pin "1") (pinfunction "1_1") (pintype "passive"))
      (node (ref "C40") (pin "2") (pinfunction "2_2") (pintype "passive"))
      (node (ref "C41") (pin "2") (pinfunction "2_2") (pintype "passive"))
      (node (ref "C43") (pin "1") (pinfunction "1_1") (pintype "passive"))
      (node (ref "C46") (pin "2") (pinfunction "2_2") (pintype "passive"))
      (node (ref "C49") (pin "2") (pinfunction "2_2") (pintype "passive"))
      (node (ref "C5") (pin "1") (pinfunction "1_1") (pintype "passive"))
      (node (ref "C50") (pin "2") (pinfunction "2_2") (pintype "passive"))
      (node (ref "C51") (pin "2") (pinfunction "2_2") (pintype "passive"))
      (node (ref "C52") (pin "1") (pinfunction "1_1") (pintype "passive"))
      (node (ref "C53") (pin "2") (pinfunction "2_2") (pintype "passive"))
      (node (ref "C54") (pin "2") (pinfunction "2_2") (pintype "passive"))
      (node (ref "C59") (pin "2") (pinfunction "2_2") (pintype "passive"))
      (node (ref "C6") (pin "2") (pinfunction "2_2") (pintype "passive"))
      (node (ref "C60") (pin "2") (pinfunction "2_2") (pintype "passive"))
      (node (ref "C61") (pin "2") (pinfunction "2_2") (pintype "passive"))
      (node (ref "C62") (pin "1") (pinfunction "1_1") (pintype "passive"))
      (node (ref "C63") (pin "2") (pinfunction "2_2") (pintype "passive"))
      (node (ref "C64") (pin "2") (pinfunction "2_2") (pintype "passive"))
      (node (ref "C69") (pin "2") (pinfunction "2_2") (pintype "passive"))
      (node (ref "C7") (pin "1") (pinfunction "1_1") (pintype "passive"))
      (node (ref "C70") (pin "2") (pinfunction "2_2") (pintype "passive"))
      (node (ref "C71") (pin "2") (pinfunction "2_2") (pintype "passive"))
      (node (ref "C72") (pin "1") (pinfunction "1_1") (pintype "passive"))
      (node (ref "C73") (pin "2") (pinfunction "2_2") (pintype "passive"))
      (node (ref "C74") (pin "2") (pinfunction "2_2") (pintype "passive"))
      (node (ref "C75") (pin "1") (pinfunction "1_1") (pintype "passive"))
      (node (ref "C76") (pin "2") (pinfunction "2_2") (pintype "passive"))
      (node (ref "C8") (pin "-") (pinfunction "-_-") (pintype "passive"))
      (node (ref "C9") (pin "1") (pinfunction "1_1") (pintype "passive"))
      (node (ref "DOA") (pin "1") (pinfunction "1_1") (pintype "passive"))
      (node (ref "DOA") (pin "5") (pinfunction "5_5") (pintype "passive"))
      (node (ref "IC1") (pin "12") (pinfunction "VSS_12") (pintype "power_in"))
      (node (ref "IC1") (pin "31") (pinfunction "VSS_31") (pintype "power_in"))
      (node (ref "IC10") (pin "6") (pinfunction "INH_6") (pintype "input"))
      (node (ref "IC10") (pin "8") (pinfunction "GND_8") (pintype "power_in"))
      (node (ref "IC11") (pin "6") (pinfunction "INH_6") (pintype "input"))
      (node (ref "IC11") (pin "8") (pinfunction "GND_8") (pintype "power_in"))
      (node (ref "IC15") (pin "12") (pinfunction "+IN_12") (pintype "input"))
      (node (ref "IC15") (pin "3") (pinfunction "+IN_3") (pintype "input"))
      (node (ref "IC16") (pin "10") (pinfunction "+IN_10") (pintype "input"))
      (node (ref "IC16") (pin "12") (pinfunction "+IN_12") (pintype "input"))
      (node (ref "IC16") (pin "3") (pinfunction "+IN_3") (pintype "input"))
      (node (ref "IC16") (pin "5") (pinfunction "+IN_5") (pintype "input"))
      (node (ref "IC17") (pin "8") (pinfunction "GND_8") (pintype "power_in"))
      (node (ref "IC18") (pin "10") (pinfunction "+IN_10") (pintype "input"))
      (node (ref "IC18") (pin "12") (pinfunction "+IN_12") (pintype "input"))
      (node (ref "IC18") (pin "3") (pinfunction "+IN_3") (pintype "input"))
      (node (ref "IC18") (pin "5") (pinfunction "+IN_5") (pintype "input"))
      (node (ref "IC19") (pin "8") (pinfunction "GND_8") (pintype "power_in"))
      (node (ref "IC2") (pin "7") (pinfunction "VSS_7") (pintype "power_in"))
      (node (ref "IC20") (pin "10") (pinfunction "+IN_10") (pintype "input"))
      (node (ref "IC20") (pin "12") (pinfunction "+IN_12") (pintype "input"))
      (node (ref "IC20") (pin "3") (pinfunction "+IN_3") (pintype "input"))
      (node (ref "IC20") (pin "5") (pinfunction "+IN_5") (pintype "input"))
      (node (ref "IC21") (pin "8") (pinfunction "GND_8") (pintype "power_in"))
      (node (ref "IC3") (pin "7") (pinfunction "VSS_7") (pintype "power_in"))
      (node (ref "IC4") (pin "7") (pinfunction "VSS_7") (pintype "power_in"))
      (node (ref "IC5") (pin "7") (pinfunction "VSS_7") (pintype "power_in"))
      (node (ref "IC6") (pin "7") (pinfunction "VSS_7") (pintype "power_in"))
      (node (ref "IC7") (pin "7") (pinfunction "VSS_7") (pintype "power_in"))
      (node (ref "IC8") (pin "6") (pinfunction "INH_6") (pintype "input"))
      (node (ref "IC8") (pin "8") (pinfunction "GND_8") (pintype "power_in"))
      (node (ref "IC9") (pin "6") (pinfunction "INH_6") (pintype "input"))
      (node (ref "IC9") (pin "8") (pinfunction "GND_8") (pintype "power_in"))
      (node (ref "PWR") (pin "5") (pinfunction "5_5") (pintype "passive"))
      (node (ref "R100") (pin "3") (pinfunction "A_3") (pintype "passive"))
      (node (ref "R101") (pin "3") (pinfunction "A_3") (pintype "passive"))
      (node (ref "R2") (pin "1") (pinfunction "1_1") (pintype "passive"))
      (node (ref "R42") (pin "2") (pinfunction "2_2") (pintype "passive"))
      (node (ref "R43") (pin "2") (pinfunction "2_2") (pintype "passive"))
      (node (ref "R48") (pin "2") (pinfunction "2_2") (pintype "passive"))
      (node (ref "R51") (pin "2") (pinfunction "2_2") (pintype "passive"))
      (node (ref "R90") (pin "3") (pinfunction "A_3") (pintype "passive"))
      (node (ref "R91") (pin "3") (pinfunction "A_3") (pintype "passive"))
      (node (ref "R92") (pin "3") (pinfunction "A_3") (pintype "passive"))
      (node (ref "R93") (pin "3") (pinfunction "A_3") (pintype "passive"))
      (node (ref "R94") (pin "3") (pinfunction "A_3") (pintype "passive"))
      (node (ref "R95") (pin "3") (pinfunction "A_3") (pintype "passive"))
      (node (ref "R96") (pin "3") (pinfunction "A_3") (pintype "passive"))
      (node (ref "R97") (pin "3") (pinfunction "A_3") (pintype "passive"))
      (node (ref "R98") (pin "3") (pinfunction "A_3") (pintype "passive"))
      (node (ref "R99") (pin "3") (pinfunction "A_3") (pintype "passive"))
      (node (ref "REF") (pin "2") (pinfunction "2_2") (pintype "passive"))
      (node (ref "U/D") (pin "1") (pinfunction "1_1") (pintype "passive"))
      (node (ref "USB") (pin "4") (pinfunction "4_4") (pintype "passive"))
      (node (ref "USB") (pin "S1") (pinfunction "S1_S1") (pintype "passive"))
      (node (ref "USB") (pin "S2") (pinfunction "S2_S2") (pintype "passive"))
    )
    (net (code "39") (name "HIV1") (class "Default")
      (node (ref "R44") (pin "2") (pinfunction "2_2") (pintype "passive"))
      (node (ref "REF") (pin "1") (pinfunction "1_1") (pintype "passive"))
    )
    (net (code "40") (name "HIV2") (class "Default")
      (node (ref "R47") (pin "2") (pinfunction "2_2") (pintype "passive"))
      (node (ref "REF") (pin "3") (pinfunction "3_3") (pintype "passive"))
    )
    (net (code "41") (name "LDAC") (class "Default")
      (node (ref "IC1") (pin "16") (pinfunction "RC1/T1OSI/ICCP2/~{UOE}_16") (pintype "bidirectional"))
      (node (ref "IC2") (pin "5") (pinfunction "~{LDAC}_5") (pintype "input"))
      (node (ref "IC3") (pin "5") (pinfunction "~{LDAC}_5") (pintype "input"))
      (node (ref "IC4") (pin "5") (pinfunction "~{LDAC}_5") (pintype "input"))
      (node (ref "IC5") (pin "5") (pinfunction "~{LDAC}_5") (pintype "input"))
      (node (ref "IC6") (pin "5") (pinfunction "~{LDAC}_5") (pintype "input"))
      (node (ref "IC7") (pin "5") (pinfunction "~{LDAC}_5") (pintype "input"))
    )
    (net (code "42") (name "M1XC") (class "Default")
      (node (ref "IC6") (pin "8") (pinfunction "VOUTA_8") (pintype "output"))
      (node (ref "R14") (pin "1") (pinfunction "1_1") (pintype "passive"))
    )
    (net (code "43") (name "M1XCF") (class "Default")
      (node (ref "C15") (pin "2") (pinfunction "2_2") (pintype "passive"))
      (node (ref "IC12") (pin "1") (pinfunction "OUT_1") (pintype "output"))
      (node (ref "IC12") (pin "2") (pinfunction "-IN_2") (pintype "input"))
      (node (ref "R41") (pin "1") (pinfunction "1_1") (pintype "passive"))
    )
    (net (code "44") (name "M1XV") (class "Default")
      (node (ref "IC9") (pin "4") (pinfunction "Z_4") (pintype "bidirectional"))
      (node (ref "R62") (pin "1") (pinfunction "1_1") (pintype "passive"))
    )
    (net (code "45") (name "M1YC") (class "Default")
      (node (ref "IC6") (pin "6") (pinfunction "VOUTB_6") (pintype "output"))
      (node (ref "R7") (pin "1") (pinfunction "1_1") (pintype "passive"))
    )
    (net (code "46") (name "M1YCF") (class "Default")
      (node (ref "C22") (pin "2") (pinfunction "2_2") (pintype "passive"))
      (node (ref "IC12") (pin "8") (pinfunction "OUT_8") (pintype "output"))
      (node (ref "IC12") (pin "9") (pinfunction "-IN_9") (pintype "input"))
      (node (ref "R32") (pin "1") (pinfunction "1_1") (pintype "passive"))
    )
    (net (code "47") (name "M1YV") (class "Default")
      (node (ref "IC10") (pin "15") (pinfunction "Y_15") (pintype "bidirectional"))
      (node (ref "R80") (pin "1") (pinfunction "1_1") (pintype "passive"))
    )
    (net (code "48") (name "M2XC") (class "Default")
      (node (ref "IC3") (pin "6") (pinfunction "VOUTB_6") (pintype "output"))
      (node (ref "R9") (pin "1") (pinfunction "1_1") (pintype "passive"))
    )
    (net (code "49") (name "M2XCF") (class "Default")
      (node (ref "C32") (pin "2") (pinfunction "2_2") (pintype "passive"))
      (node (ref "IC13") (pin "8") (pinfunction "OUT_8") (pintype "output"))
      (node (ref "IC13") (pin "9") (pinfunction "-IN_9") (pintype "input"))
      (node (ref "R23") (pin "1") (pinfunction "1_1") (pintype "passive"))
    )
    (net (code "50") (name "M2XV") (class "Default")
      (node (ref "IC10") (pin "4") (pinfunction "Z_4") (pintype "bidirectional"))
      (node (ref "R72") (pin "1") (pinfunction "1_1") (pintype "passive"))
    )
    (net (code "51") (name "M2YC") (class "Default")
      (node (ref "IC3") (pin "8") (pinfunction "VOUTA_8") (pintype "output"))
      (node (ref "R22") (pin "1") (pinfunction "1_1") (pintype "passive"))
    )
    (net (code "52") (name "M2YCF") (class "Default")
      (node (ref "C23") (pin "2") (pinfunction "2_2") (pintype "passive"))
      (node (ref "IC13") (pin "1") (pinfunction "OUT_1") (pintype "output"))
      (node (ref "IC13") (pin "2") (pinfunction "-IN_2") (pintype "input"))
      (node (ref "R15") (pin "1") (pinfunction "1_1") (pintype "passive"))
    )
    (net (code "53") (name "M2YV") (class "Default")
      (node (ref "IC9") (pin "15") (pinfunction "Y_15") (pintype "bidirectional"))
      (node (ref "R70") (pin "1") (pinfunction "1_1") (pintype "passive"))
    )
    (net (code "54") (name "M3XC") (class "Default")
      (node (ref "IC4") (pin "6") (pinfunction "VOUTB_6") (pintype "output"))
      (node (ref "R10") (pin "1") (pinfunction "1_1") (pintype "passive"))
    )
    (net (code "55") (name "M3XCF") (class "Default")
      (node (ref "C36") (pin "2") (pinfunction "2_2") (pintype "passive"))
      (node (ref "IC14") (pin "6") (pinfunction "-IN_6") (pintype "input"))
      (node (ref "IC14") (pin "7") (pinfunction "OUT_7") (pintype "output"))
      (node (ref "R24") (pin "1") (pinfunction "1_1") (pintype "passive"))
    )
    (net (code "56") (name "M3XV") (class "Default")
      (node (ref "IC10") (pin "14") (pinfunction "X_14") (pintype "bidirectional"))
      (node (ref "R74") (pin "1") (pinfunction "1_1") (pintype "passive"))
    )
    (net (code "57") (name "M3YC") (class "Default")
      (node (ref "IC4") (pin "8") (pinfunction "VOUTA_8") (pintype "output"))
      (node (ref "R30") (pin "1") (pinfunction "1_1") (pintype "passive"))
    )
    (net (code "58") (name "M3YCF") (class "Default")
      (node (ref "C33") (pin "2") (pinfunction "2_2") (pintype "passive"))
      (node (ref "IC14") (pin "1") (pinfunction "OUT_1") (pintype "output"))
      (node (ref "IC14") (pin "2") (pinfunction "-IN_2") (pintype "input"))
      (node (ref "R19") (pin "1") (pinfunction "1_1") (pintype "passive"))
    )
    (net (code "59") (name "M3YV") (class "Default")
      (node (ref "IC9") (pin "14") (pinfunction "X_14") (pintype "bidirectional"))
      (node (ref "R68") (pin "1") (pinfunction "1_1") (pintype "passive"))
    )
    (net (code "60") (name "MCLR") (class "Default")
      (node (ref "DOA") (pin "3") (pinfunction "3_3") (pintype "passive"))
      (node (ref "IC1") (pin "1") (pinfunction "~{MCLR}/VPP/RE3_1") (pintype "input"))
      (node (ref "R5") (pin "1") (pinfunction "1_1") (pintype "passive"))
    )
    (net (code "61") (name "MIL_I") (class "Default")
      (node (ref "IC10") (pin "1") (pinfunction "Y1_1") (pintype "bidirectional"))
      (node (ref "IC10") (pin "13") (pinfunction "X1_13") (pintype "bidirectional"))
      (node (ref "IC10") (pin "3") (pinfunction "Z1_3") (pintype "bidirectional"))
      (node (ref "IC15") (pin "1") (pinfunction "OUT_1") (pintype "output"))
      (node (ref "IC9") (pin "1") (pinfunction "Y1_1") (pintype "bidirectional"))
      (node (ref "IC9") (pin "13") (pinfunction "X1_13") (pintype "bidirectional"))
      (node (ref "IC9") (pin "3") (pinfunction "Z1_3") (pintype "bidirectional"))
      (node (ref "R88") (pin "2") (pinfunction "S_2") (pintype "passive"))
      (node (ref "R88") (pin "3") (pinfunction "A_3") (pintype "passive"))
      (node (ref "TP1") (pin "TP") (pinfunction "TP_TP") (pintype "input"))
    )
    (net (code "62") (name "MIL_N") (class "Default")
      (node (ref "IC10") (pin "12") (pinfunction "X0_12") (pintype "bidirectional"))
      (node (ref "IC10") (pin "2") (pinfunction "Y0_2") (pintype "bidirectional"))
      (node (ref "IC10") (pin "5") (pinfunction "Z0_5") (pintype "bidirectional"))
      (node (ref "IC15") (pin "7") (pinfunction "OUT_7") (pintype "output"))
      (node (ref "IC9") (pin "12") (pinfunction "X0_12") (pintype "bidirectional"))
      (node (ref "IC9") (pin "2") (pinfunction "Y0_2") (pintype "bidirectional"))
      (node (ref "IC9") (pin "5") (pinfunction "Z0_5") (pintype "bidirectional"))
      (node (ref "R45") (pin "1") (pinfunction "1_1") (pintype "passive"))
      (node (ref "TP2") (pin "TP") (pinfunction "TP_TP") (pintype "input"))
    )
    (net (code "63") (name "MRB5") (class "Default")
      (node (ref "IC1") (pin "38") (pinfunction "RB5/KBI1/PGM_38") (pintype "bidirectional"))
      (node (ref "IC9") (pin "11") (pinfunction "A_11") (pintype "input"))
    )
    (net (code "64") (name "MRB6") (class "Default")
      (node (ref "IC1") (pin "39") (pinfunction "RB6/KBI2/PGC_39") (pintype "bidirectional"))
      (node (ref "IC9") (pin "10") (pinfunction "B_10") (pintype "input"))
    )
    (net (code "65") (name "MRB7") (class "Default")
      (node (ref "IC1") (pin "40") (pinfunction "RB7/BKI3/PGD_40") (pintype "bidirectional"))
      (node (ref "IC9") (pin "9") (pinfunction "C_9") (pintype "input"))
    )
    (net (code "66") (name "MRD4") (class "Default")
      (node (ref "IC1") (pin "27") (pinfunction "RD4/SPP4_27") (pintype "bidirectional"))
      (node (ref "IC10") (pin "11") (pinfunction "A_11") (pintype "input"))
    )
    (net (code "67") (name "MRD5") (class "Default")
      (node (ref "IC1") (pin "28") (pinfunction "RD5/SPP5/P1B_28") (pintype "bidirectional"))
      (node (ref "IC10") (pin "10") (pinfunction "B_10") (pintype "input"))
    )
    (net (code "68") (name "MRD6") (class "Default")
      (node (ref "IC1") (pin "29") (pinfunction "RD6/SPP6/P1C_29") (pintype "bidirectional"))
      (node (ref "IC10") (pin "9") (pinfunction "C_9") (pintype "input"))
    )
    (net (code "69") (name "Net-(C15-Pad1)") (class "Default")
      (node (ref "C15") (pin "1") (pinfunction "1_1") (pintype "passive"))
      (node (ref "R13") (pin "1") (pinfunction "1_1") (pintype "passive"))
      (node (ref "R14") (pin "2") (pinfunction "2_2") (pintype "passive"))
    )
    (net (code "70") (name "Net-(C18-Pad1)") (class "Default")
      (node (ref "C18") (pin "1") (pinfunction "1_1") (pintype "passive"))
      (node (ref "R12") (pin "1") (pinfunction "1_1") (pintype "passive"))
      (node (ref "R6") (pin "2") (pinfunction "2_2") (pintype "passive"))
    )
    (net (code "71") (name "Net-(C19-Pad1)") (class "Default")
      (node (ref "C19") (pin "1") (pinfunction "1_1") (pintype "passive"))
      (node (ref "R17") (pin "1") (pinfunction "1_1") (pintype "passive"))
      (node (ref "R18") (pin "2") (pinfunction "2_2") (pintype "passive"))
    )
    (net (code "72") (name "Net-(C22-Pad1)") (class "Default")
      (node (ref "C22") (pin "1") (pinfunction "1_1") (pintype "passive"))
      (node (ref "R16") (pin "1") (pinfunction "1_1") (pintype "passive"))
      (node (ref "R7") (pin "2") (pinfunction "2_2") (pintype "passive"))
    )
    (net (code "73") (name "Net-(C23-Pad1)") (class "Default")
      (node (ref "C23") (pin "1") (pinfunction "1_1") (pintype "passive"))
      (node (ref "R21") (pin "1") (pinfunction "1_1") (pintype "passive"))
      (node (ref "R22") (pin "2") (pinfunction "2_2") (pintype "passive"))
    )
    (net (code "74") (name "Net-(C26-Pad1)") (class "Default")
      (node (ref "C26") (pin "1") (pinfunction "1_1") (pintype "passive"))
      (node (ref "R20") (pin "1") (pinfunction "1_1") (pintype "passive"))
      (node (ref "R8") (pin "2") (pinfunction "2_2") (pintype "passive"))
    )
    (net (code "75") (name "Net-(C29-Pad1)") (class "Default")
      (node (ref "C29") (pin "1") (pinfunction "1_1") (pintype "passive"))
      (node (ref "R26") (pin "1") (pinfunction "1_1") (pintype "passive"))
      (node (ref "R27") (pin "2") (pinfunction "2_2") (pintype "passive"))
    )
    (net (code "76") (name "Net-(C32-Pad1)") (class "Default")
      (node (ref "C32") (pin "1") (pinfunction "1_1") (pintype "passive"))
      (node (ref "R25") (pin "1") (pinfunction "1_1") (pintype "passive"))
      (node (ref "R9") (pin "2") (pinfunction "2_2") (pintype "passive"))
    )
    (net (code "77") (name "Net-(C33-Pad1)") (class "Default")
      (node (ref "C33") (pin "1") (pinfunction "1_1") (pintype "passive"))
      (node (ref "R29") (pin "1") (pinfunction "1_1") (pintype "passive"))
      (node (ref "R30") (pin "2") (pinfunction "2_2") (pintype "passive"))
    )
    (net (code "78") (name "Net-(C36-Pad1)") (class "Default")
      (node (ref "C36") (pin "1") (pinfunction "1_1") (pintype "passive"))
      (node (ref "R10") (pin "2") (pinfunction "2_2") (pintype "passive"))
      (node (ref "R28") (pin "1") (pinfunction "1_1") (pintype "passive"))
    )
    (net (code "79") (name "Net-(C39-Pad1)") (class "Default")
      (node (ref "C39") (pin "1") (pinfunction "1_1") (pintype "passive"))
      (node (ref "R36") (pin "1") (pinfunction "1_1") (pintype "passive"))
      (node (ref "R37") (pin "2") (pinfunction "2_2") (pintype "passive"))
    )
    (net (code "80") (name "Net-(C42-Pad1)") (class "Default")
      (node (ref "C42") (pin "1") (pinfunction "1_1") (pintype "passive"))
      (node (ref "R11") (pin "2") (pinfunction "2_2") (pintype "passive"))
      (node (ref "R35") (pin "1") (pinfunction "1_1") (pintype "passive"))
    )
    (net (code "81") (name "Net-(C49-Pad1)") (class "Default")
      (node (ref "C49") (pin "1") (pinfunction "1_1") (pintype "passive"))
      (node (ref "R57") (pin "1") (pinfunction "1_1") (pintype "passive"))
    )
    (net (code "82") (name "Net-(C50-Pad1)") (class "Default")
      (node (ref "C50") (pin "1") (pinfunction "1_1") (pintype "passive"))
      (node (ref "R59") (pin "1") (pinfunction "1_1") (pintype "passive"))
    )
    (net (code "83") (name "Net-(C53-Pad1)") (class "Default")
      (node (ref "C53") (pin "1") (pinfunction "1_1") (pintype "passive"))
      (node (ref "R61") (pin "1") (pinfunction "1_1") (pintype "passive"))
    )
    (net (code "84") (name "Net-(C54-Pad1)") (class "Default")
      (node (ref "C54") (pin "1") (pinfunction "1_1") (pintype "passive"))
      (node (ref "R63") (pin "1") (pinfunction "1_1") (pintype "passive"))
    )
    (net (code "85") (name "Net-(C59-Pad1)") (class "Default")
      (node (ref "C59") (pin "1") (pinfunction "1_1") (pintype "passive"))
      (node (ref "R69") (pin "1") (pinfunction "1_1") (pintype "passive"))
    )
    (net (code "86") (name "Net-(C60-Pad1)") (class "Default")
      (node (ref "C60") (pin "1") (pinfunction "1_1") (pintype "passive"))
      (node (ref "R71") (pin "1") (pinfunction "1_1") (pintype "passive"))
    )
    (net (code "87") (name "Net-(C63-Pad1)") (class "Default")
      (node (ref "C63") (pin "1") (pinfunction "1_1") (pintype "passive"))
      (node (ref "R73") (pin "1") (pinfunction "1_1") (pintype "passive"))
    )
    (net (code "88") (name "Net-(C64-Pad1)") (class "Default")
      (node (ref "C64") (pin "1") (pinfunction "1_1") (pintype "passive"))
      (node (ref "R75") (pin "1") (pinfunction "1_1") (pintype "passive"))
    )
    (net (code "89") (name "Net-(C69-Pad1)") (class "Default")
      (node (ref "C69") (pin "1") (pinfunction "1_1") (pintype "passive"))
      (node (ref "R81") (pin "1") (pinfunction "1_1") (pintype "passive"))
    )
    (net (code "90") (name "Net-(C70-Pad1)") (class "Default")
      (node (ref "C70") (pin "1") (pinfunction "1_1") (pintype "passive"))
      (node (ref "R83") (pin "1") (pinfunction "1_1") (pintype "passive"))
    )
    (net (code "91") (name "Net-(C73-Pad1)") (class "Default")
      (node (ref "C73") (pin "1") (pinfunction "1_1") (pintype "passive"))
      (node (ref "R85") (pin "1") (pinfunction "1_1") (pintype "passive"))
    )
    (net (code "92") (name "Net-(C74-Pad1)") (class "Default")
      (node (ref "C74") (pin "1") (pinfunction "1_1") (pintype "passive"))
      (node (ref "R87") (pin "1") (pinfunction "1_1") (pintype "passive"))
    )
    (net (code "93") (name "Net-(DIAG-C)") (class "Default")
      (node (ref "DIAG") (pin "K") (pinfunction "C_K") (pintype "passive"))
      (node (ref "R4") (pin "1") (pinfunction "1_1") (pintype "passive"))
    )
    (net (code "94") (name "Net-(IC1-OSC1{slash}CLKI)") (class "Default")
      (node (ref "C4") (pin "2") (pinfunction "2_2") (pintype "passive"))
      (node (ref "IC1") (pin "13") (pinfunction "OSC1/CLKI_13") (pintype "input"))
      (node (ref "Q1") (pin "2") (pinfunction "2_2") (pintype "passive"))
    )
    (net (code "95") (name "Net-(IC1-RA1{slash}AN1)") (class "Default")
      (node (ref "D1") (pin "A") (pinfunction "A_A") (pintype "passive"))
      (node (ref "IC1") (pin "3") (pinfunction "RA1/AN1_3") (pintype "bidirectional"))
      (node (ref "K1") (pin "5") (pinfunction "-_5") (pintype "passive"))
    )
    (net (code "96") (name "Net-(IC1-RA6{slash}OSC2{slash}CLKO)") (class "Default")
      (node (ref "C5") (pin "2") (pinfunction "2_2") (pintype "passive"))
      (node (ref "IC1") (pin "14") (pinfunction "RA6/OSC2/CLKO_14") (pintype "output"))
      (node (ref "Q1") (pin "1") (pinfunction "1_1") (pintype "passive"))
    )
    (net (code "97") (name "Net-(IC1-RC2{slash}CCP1{slash}P1A)") (class "Default")
      (node (ref "IC1") (pin "17") (pinfunction "RC2/CCP1/P1A_17") (pintype "bidirectional"))
      (node (ref "R1") (pin "2") (pinfunction "2_2") (pintype "passive"))
      (node (ref "R2") (pin "2") (pinfunction "2_2") (pintype "passive"))
    )
    (net (code "98") (name "Net-(IC1-RD0{slash}SPP0)") (class "Default")
      (node (ref "IC1") (pin "19") (pinfunction "RD0/SPP0_19") (pintype "bidirectional"))
      (node (ref "OUT") (pin "2") (pinfunction "2_2") (pintype "passive"))
    )
    (net (code "99") (name "Net-(IC1-RD1{slash}SPP1)") (class "Default")
      (node (ref "IC1") (pin "20") (pinfunction "RD1/SPP1_20") (pintype "bidirectional"))
      (node (ref "OUT") (pin "1") (pinfunction "1_1") (pintype "passive"))
    )
    (net (code "100") (name "Net-(IC1-VUSB)") (class "Default")
      (node (ref "C6") (pin "1") (pinfunction "1_1") (pintype "passive"))
      (node (ref "IC1") (pin "18") (pinfunction "VUSB_18") (pintype "bidirectional"))
    )
    (net (code "101") (name "Net-(IC12A-+IN)") (class "Default")
      (node (ref "C16") (pin "1") (pinfunction "1_1") (pintype "passive"))
      (node (ref "IC12") (pin "3") (pinfunction "+IN_3") (pintype "input"))
      (node (ref "R13") (pin "2") (pinfunction "2_2") (pintype "passive"))
    )
    (net (code "102") (name "Net-(IC12B-+IN)") (class "Default")
      (node (ref "C17") (pin "1") (pinfunction "1_1") (pintype "passive"))
      (node (ref "IC12") (pin "5") (pinfunction "+IN_5") (pintype "input"))
      (node (ref "R12") (pin "2") (pinfunction "2_2") (pintype "passive"))
    )
    (net (code "103") (name "Net-(IC12C-+IN)") (class "Default")
      (node (ref "C21") (pin "1") (pinfunction "1_1") (pintype "passive"))
      (node (ref "IC12") (pin "10") (pinfunction "+IN_10") (pintype "input"))
      (node (ref "R16") (pin "2") (pinfunction "2_2") (pintype "passive"))
    )
    (net (code "104") (name "Net-(IC12D-+IN)") (class "Default")
      (node (ref "C20") (pin "1") (pinfunction "1_1") (pintype "passive"))
      (node (ref "IC12") (pin "12") (pinfunction "+IN_12") (pintype "input"))
      (node (ref "R17") (pin "2") (pinfunction "2_2") (pintype "passive"))
    )
    (net (code "105") (name "Net-(IC13A-+IN)") (class "Default")
      (node (ref "C24") (pin "1") (pinfunction "1_1") (pintype "passive"))
      (node (ref "IC13") (pin "3") (pinfunction "+IN_3") (pintype "input"))
      (node (ref "R21") (pin "2") (pinfunction "2_2") (pintype "passive"))
    )
    (net (code "106") (name "Net-(IC13B-+IN)") (class "Default")
      (node (ref "C25") (pin "1") (pinfunction "1_1") (pintype "passive"))
      (node (ref "IC13") (pin "5") (pinfunction "+IN_5") (pintype "input"))
      (node (ref "R20") (pin "2") (pinfunction "2_2") (pintype "passive"))
    )
    (net (code "107") (name "Net-(IC13C-+IN)") (class "Default")
      (node (ref "C31") (pin "1") (pinfunction "1_1") (pintype "passive"))
      (node (ref "IC13") (pin "10") (pinfunction "+IN_10") (pintype "input"))
      (node (ref "R25") (pin "2") (pinfunction "2_2") (pintype "passive"))
    )
    (net (code "108") (name "Net-(IC13D-+IN)") (class "Default")
      (node (ref "C30") (pin "1") (pinfunction "1_1") (pintype "passive"))
      (node (ref "IC13") (pin "12") (pinfunction "+IN_12") (pintype "input"))
      (node (ref "R26") (pin "2") (pinfunction "2_2") (pintype "passive"))
    )
    (net (code "109") (name "Net-(IC14A-+IN)") (class "Default")
      (node (ref "C34") (pin "1") (pinfunction "1_1") (pintype "passive"))
      (node (ref "IC14") (pin "3") (pinfunction "+IN_3") (pintype "input"))
      (node (ref "R29") (pin "2") (pinfunction "2_2") (pintype "passive"))
    )
    (net (code "110") (name "Net-(IC14B-+IN)") (class "Default")
      (node (ref "C35") (pin "1") (pinfunction "1_1") (pintype "passive"))
      (node (ref "IC14") (pin "5") (pinfunction "+IN_5") (pintype "input"))
      (node (ref "R28") (pin "2") (pinfunction "2_2") (pintype "passive"))
    )
    (net (code "111") (name "Net-(IC14C-+IN)") (class "Default")
      (node (ref "C41") (pin "1") (pinfunction "1_1") (pintype "passive"))
      (node (ref "IC14") (pin "10") (pinfunction "+IN_10") (pintype "input"))
      (node (ref "R35") (pin "2") (pinfunction "2_2") (pintype "passive"))
    )
    (net (code "112") (name "Net-(IC14D-+IN)") (class "Default")
      (node (ref "C40") (pin "1") (pinfunction "1_1") (pintype "passive"))
      (node (ref "IC14") (pin "12") (pinfunction "+IN_12") (pintype "input"))
      (node (ref "R36") (pin "2") (pinfunction "2_2") (pintype "passive"))
    )
    (net (code "113") (name "Net-(IC15A--IN)") (class "Default")
      (node (ref "IC15") (pin "2") (pinfunction "-IN_2") (pintype "input"))
      (node (ref "R102") (pin "2") (pinfunction "2_2") (pintype "passive"))
      (node (ref "R46") (pin "2") (pinfunction "2_2") (pintype "passive"))
    )
    (net (code "114") (name "Net-(IC15B-+IN)") (class "Default")
      (node (ref "IC15") (pin "5") (pinfunction "+IN_5") (pintype "input"))
      (node (ref "R103") (pin "2") (pinfunction "2_2") (pintype "passive"))
    )
    (net (code "115") (name "Net-(IC15B--IN)") (class "Default")
      (node (ref "IC15") (pin "6") (pinfunction "-IN_6") (pintype "input"))
      (node (ref "R42") (pin "1") (pinfunction "1_1") (pintype "passive"))
      (node (ref "R45") (pin "2") (pinfunction "2_2") (pintype "passive"))
    )
    (net (code "116") (name "Net-(IC15C-+IN)") (class "Default")
      (node (ref "IC15") (pin "10") (pinfunction "+IN_10") (pintype "input"))
      (node (ref "R105") (pin "2") (pinfunction "2_2") (pintype "passive"))
    )
    (net (code "117") (name "Net-(IC15C--IN)") (class "Default")
      (node (ref "IC15") (pin "9") (pinfunction "-IN_9") (pintype "input"))
      (node (ref "R49") (pin "2") (pinfunction "2_2") (pintype "passive"))
      (node (ref "R51") (pin "1") (pinfunction "1_1") (pintype "passive"))
    )
    (net (code "118") (name "Net-(IC15D--IN)") (class "Default")
      (node (ref "IC15") (pin "13") (pinfunction "-IN_13") (pintype "input"))
      (node (ref "R104") (pin "2") (pinfunction "2_2") (pintype "passive"))
      (node (ref "R50") (pin "2") (pinfunction "2_2") (pintype "passive"))
    )
    (net (code "119") (name "Net-(IC16A--IN)") (class "Default")
      (node (ref "C44") (pin "1") (pinfunction "1_1") (pintype "passive"))
      (node (ref "IC16") (pin "2") (pinfunction "-IN_2") (pintype "input"))
      (node (ref "IC17") (pin "13") (pinfunction "OUT_13") (pintype "output"))
      (node (ref "R53") (pin "1") (pinfunction "1_1") (pintype "passive"))
    )
    (net (code "120") (name "Net-(IC16A-OUT)") (class "Default")
      (node (ref "C44") (pin "2") (pinfunction "2_2") (pintype "passive"))
      (node (ref "IC16") (pin "1") (pinfunction "OUT_1") (pintype "output"))
      (node (ref "R53") (pin "2") (pinfunction "2_2") (pintype "passive"))
      (node (ref "R93") (pin "1") (pinfunction "E_1") (pintype "passive"))
    )
    (net (code "121") (name "Net-(IC16B--IN)") (class "Default")
      (node (ref "C45") (pin "1") (pinfunction "1_1") (pintype "passive"))
      (node (ref "IC16") (pin "6") (pinfunction "-IN_6") (pintype "input"))
      (node (ref "IC17") (pin "12") (pinfunction "OUT_12") (pintype "output"))
      (node (ref "R52") (pin "1") (pinfunction "1_1") (pintype "passive"))
    )
    (net (code "122") (name "Net-(IC16B-OUT)") (class "Default")
      (node (ref "C45") (pin "2") (pinfunction "2_2") (pintype "passive"))
      (node (ref "IC16") (pin "7") (pinfunction "OUT_7") (pintype "output"))
      (node (ref "R52") (pin "2") (pinfunction "2_2") (pintype "passive"))
      (node (ref "R91") (pin "1") (pinfunction "E_1") (pintype "passive"))
    )
    (net (code "123") (name "Net-(IC16C--IN)") (class "Default")
      (node (ref "C48") (pin "1") (pinfunction "1_1") (pintype "passive"))
      (node (ref "IC16") (pin "9") (pinfunction "-IN_9") (pintype "input"))
      (node (ref "IC17") (pin "5") (pinfunction "OUT_5") (pintype "output"))
      (node (ref "R54") (pin "1") (pinfunction "1_1") (pintype "passive"))
    )
    (net (code "124") (name "Net-(IC16C-OUT)") (class "Default")
      (node (ref "C48") (pin "2") (pinfunction "2_2") (pintype "passive"))
      (node (ref "IC16") (pin "8") (pinfunction "OUT_8") (pintype "output"))
      (node (ref "R54") (pin "2") (pinfunction "2_2") (pintype "passive"))
      (node (ref "R92") (pin "1") (pinfunction "E_1") (pintype "passive"))
    )
    (net (code "125") (name "Net-(IC16D--IN)") (class "Default")
      (node (ref "C47") (pin "1") (pinfunction "1_1") (pintype "passive"))
      (node (ref "IC16") (pin "13") (pinfunction "-IN_13") (pintype "input"))
      (node (ref "IC17") (pin "4") (pinfunction "OUT_4") (pintype "output"))
      (node (ref "R55") (pin "1") (pinfunction "1_1") (pintype "passive"))
    )
    (net (code "126") (name "Net-(IC16D-OUT)") (class "Default")
      (node (ref "C47") (pin "2") (pinfunction "2_2") (pintype "passive"))
      (node (ref "IC16") (pin "14") (pinfunction "OUT_14") (pintype "output"))
      (node (ref "R55") (pin "2") (pinfunction "2_2") (pintype "passive"))
      (node (ref "R90") (pin "1") (pinfunction "E_1") (pintype "passive"))
    )
    (net (code "127") (name "Net-(IC17A-CTRL)") (class "Default")
      (node (ref "IC17") (pin "3") (pinfunction "CTRL_3") (pintype "input"))
      (node (ref "R39") (pin "2") (pinfunction "2_2") (pintype "passive"))
    )
    (net (code "128") (name "Net-(IC17A-IN)") (class "Default")
      (node (ref "IC17") (pin "2") (pinfunction "IN_2") (pintype "input"))
      (node (ref "R58") (pin "2") (pinfunction "2_2") (pintype "passive"))
      (node (ref "R59") (pin "2") (pinfunction "2_2") (pintype "passive"))
    )
    (net (code "129") (name "Net-(IC17B-CTRL)") (class "Default")
      (node (ref "IC17") (pin "6") (pinfunction "CTRL_6") (pintype "input"))
      (node (ref "R38") (pin "2") (pinfunction "2_2") (pintype "passive"))
    )
    (net (code "130") (name "Net-(IC17B-IN)") (class "Default")
      (node (ref "IC17") (pin "7") (pinfunction "IN_7") (pintype "input"))
      (node (ref "R56") (pin "2") (pinfunction "2_2") (pintype "passive"))
      (node (ref "R57") (pin "2") (pinfunction "2_2") (pintype "passive"))
    )
    (net (code "131") (name "Net-(IC17C-CTRL)") (class "Default")
      (node (ref "IC17") (pin "11") (pinfunction "CTRL_11") (pintype "input"))
      (node (ref "R40") (pin "2") (pinfunction "2_2") (pintype "passive"))
    )
    (net (code "132") (name "Net-(IC17C-IN)") (class "Default")
      (node (ref "IC17") (pin "10") (pinfunction "IN_10") (pintype "input"))
      (node (ref "R60") (pin "2") (pinfunction "2_2") (pintype "passive"))
      (node (ref "R61") (pin "2") (pinfunction "2_2") (pintype "passive"))
    )
    (net (code "133") (name "Net-(IC17D-CTRL)") (class "Default")
      (node (ref "IC17") (pin "14") (pinfunction "CTRL_14") (pintype "input"))
      (node (ref "R41") (pin "2") (pinfunction "2_2") (pintype "passive"))
    )
    (net (code "134") (name "Net-(IC17D-IN)") (class "Default")
      (node (ref "IC17") (pin "15") (pinfunction "IN_15") (pintype "input"))
      (node (ref "R62") (pin "2") (pinfunction "2_2") (pintype "passive"))
      (node (ref "R63") (pin "2") (pinfunction "2_2") (pintype "passive"))
    )
    (net (code "135") (name "Net-(IC18A--IN)") (class "Default")
      (node (ref "C55") (pin "1") (pinfunction "1_1") (pintype "passive"))
      (node (ref "IC18") (pin "2") (pinfunction "-IN_2") (pintype "input"))
      (node (ref "IC19") (pin "13") (pinfunction "OUT_13") (pintype "output"))
      (node (ref "R65") (pin "1") (pinfunction "1_1") (pintype "passive"))
    )
    (net (code "136") (name "Net-(IC18A-OUT)") (class "Default")
      (node (ref "C55") (pin "2") (pinfunction "2_2") (pintype "passive"))
      (node (ref "IC18") (pin "1") (pinfunction "OUT_1") (pintype "output"))
      (node (ref "R65") (pin "2") (pinfunction "2_2") (pintype "passive"))
      (node (ref "R95") (pin "1") (pinfunction "E_1") (pintype "passive"))
    )
    (net (code "137") (name "Net-(IC18B--IN)") (class "Default")
      (node (ref "C56") (pin "1") (pinfunction "1_1") (pintype "passive"))
      (node (ref "IC18") (pin "6") (pinfunction "-IN_6") (pintype "input"))
      (node (ref "IC19") (pin "12") (pinfunction "OUT_12") (pintype "output"))
      (node (ref "R64") (pin "1") (pinfunction "1_1") (pintype "passive"))
    )
    (net (code "138") (name "Net-(IC18B-OUT)") (class "Default")
      (node (ref "C56") (pin "2") (pinfunction "2_2") (pintype "passive"))
      (node (ref "IC18") (pin "7") (pinfunction "OUT_7") (pintype "output"))
      (node (ref "R64") (pin "2") (pinfunction "2_2") (pintype "passive"))
      (node (ref "R94") (pin "1") (pinfunction "E_1") (pintype "passive"))
    )
    (net (code "139") (name "Net-(IC18C--IN)") (class "Default")
      (node (ref "C58") (pin "1") (pinfunction "1_1") (pintype "passive"))
      (node (ref "IC18") (pin "9") (pinfunction "-IN_9") (pintype "input"))
      (node (ref "IC19") (pin "5") (pinfunction "OUT_5") (pintype "output"))
      (node (ref "R66") (pin "1") (pinfunction "1_1") (pintype "passive"))
    )
    (net (code "140") (name "Net-(IC18C-OUT)") (class "Default")
      (node (ref "C58") (pin "2") (pinfunction "2_2") (pintype "passive"))
      (node (ref "IC18") (pin "8") (pinfunction "OUT_8") (pintype "output"))
      (node (ref "R66") (pin "2") (pinfunction "2_2") (pintype "passive"))
      (node (ref "R96") (pin "1") (pinfunction "E_1") (pintype "passive"))
    )
    (net (code "141") (name "Net-(IC18D--IN)") (class "Default")
      (node (ref "C57") (pin "1") (pinfunction "1_1") (pintype "passive"))
      (node (ref "IC18") (pin "13") (pinfunction "-IN_13") (pintype "input"))
      (node (ref "IC19") (pin "4") (pinfunction "OUT_4") (pintype "output"))
      (node (ref "R67") (pin "1") (pinfunction "1_1") (pintype "passive"))
    )
    (net (code "142") (name "Net-(IC18D-OUT)") (class "Default")
      (node (ref "C57") (pin "2") (pinfunction "2_2") (pintype "passive"))
      (node (ref "IC18") (pin "14") (pinfunction "OUT_14") (pintype "output"))
      (node (ref "R67") (pin "2") (pinfunction "2_2") (pintype "passive"))
      (node (ref "R97") (pin "1") (pinfunction "E_1") (pintype "passive"))
    )
    (net (code "143") (name "Net-(IC19A-CTRL)") (class "Default")
      (node (ref "IC19") (pin "3") (pinfunction "CTRL_3") (pintype "input"))
      (node (ref "R15") (pin "2") (pinfunction "2_2") (pintype "passive"))
    )
    (net (code "144") (name "Net-(IC19A-IN)") (class "Default")
      (node (ref "IC19") (pin "2") (pinfunction "IN_2") (pintype "input"))
      (node (ref "R70") (pin "2") (pinfunction "2_2") (pintype "passive"))
      (node (ref "R71") (pin "2") (pinfunction "2_2") (pintype "passive"))
    )
    (net (code "145") (name "Net-(IC19B-CTRL)") (class "Default")
      (node (ref "IC19") (pin "6") (pinfunction "CTRL_6") (pintype "input"))
      (node (ref "R19") (pin "2") (pinfunction "2_2") (pintype "passive"))
    )
    (net (code "146") (name "Net-(IC19B-IN)") (class "Default")
      (node (ref "IC19") (pin "7") (pinfunction "IN_7") (pintype "input"))
      (node (ref "R68") (pin "2") (pinfunction "2_2") (pintype "passive"))
      (node (ref "R69") (pin "2") (pinfunction "2_2") (pintype "passive"))
    )
    (net (code "147") (name "Net-(IC19C-CTRL)") (class "Default")
      (node (ref "IC19") (pin "11") (pinfunction "CTRL_11") (pintype "input"))
      (node (ref "R23") (pin "2") (pinfunction "2_2") (pintype "passive"))
    )
    (net (code "148") (name "Net-(IC19C-IN)") (class "Default")
      (node (ref "IC19") (pin "10") (pinfunction "IN_10") (pintype "input"))
      (node (ref "R72") (pin "2") (pinfunction "2_2") (pintype "passive"))
      (node (ref "R73") (pin "2") (pinfunction "2_2") (pintype "passive"))
    )
    (net (code "149") (name "Net-(IC19D-CTRL)") (class "Default")
      (node (ref "IC19") (pin "14") (pinfunction "CTRL_14") (pintype "input"))
      (node (ref "R24") (pin "2") (pinfunction "2_2") (pintype "passive"))
    )
    (net (code "150") (name "Net-(IC19D-IN)") (class "Default")
      (node (ref "IC19") (pin "15") (pinfunction "IN_15") (pintype "input"))
      (node (ref "R74") (pin "2") (pinfunction "2_2") (pintype "passive"))
      (node (ref "R75") (pin "2") (pinfunction "2_2") (pintype "passive"))
    )
    (net (code "151") (name "Net-(IC20A--IN)") (class "Default")
      (node (ref "C65") (pin "1") (pinfunction "1_1") (pintype "passive"))
      (node (ref "IC20") (pin "2") (pinfunction "-IN_2") (pintype "input"))
      (node (ref "IC21") (pin "13") (pinfunction "OUT_13") (pintype "output"))
      (node (ref "R77") (pin "1") (pinfunction "1_1") (pintype "passive"))
    )
    (net (code "152") (name "Net-(IC20A-OUT)") (class "Default")
      (node (ref "C65") (pin "2") (pinfunction "2_2") (pintype "passive"))
      (node (ref "IC20") (pin "1") (pinfunction "OUT_1") (pintype "output"))
      (node (ref "R100") (pin "1") (pinfunction "E_1") (pintype "passive"))
      (node (ref "R77") (pin "2") (pinfunction "2_2") (pintype "passive"))
    )
    (net (code "153") (name "Net-(IC20B--IN)") (class "Default")
      (node (ref "C66") (pin "1") (pinfunction "1_1") (pintype "passive"))
      (node (ref "IC20") (pin "6") (pinfunction "-IN_6") (pintype "input"))
      (node (ref "IC21") (pin "12") (pinfunction "OUT_12") (pintype "output"))
      (node (ref "R76") (pin "1") (pinfunction "1_1") (pintype "passive"))
    )
    (net (code "154") (name "Net-(IC20B-OUT)") (class "Default")
      (node (ref "C66") (pin "2") (pinfunction "2_2") (pintype "passive"))
      (node (ref "IC20") (pin "7") (pinfunction "OUT_7") (pintype "output"))
      (node (ref "R76") (pin "2") (pinfunction "2_2") (pintype "passive"))
      (node (ref "R99") (pin "1") (pinfunction "E_1") (pintype "passive"))
    )
    (net (code "155") (name "Net-(IC20C--IN)") (class "Default")
      (node (ref "C68") (pin "1") (pinfunction "1_1") (pintype "passive"))
      (node (ref "IC20") (pin "9") (pinfunction "-IN_9") (pintype "input"))
      (node (ref "IC21") (pin "5") (pinfunction "OUT_5") (pintype "output"))
      (node (ref "R78") (pin "1") (pinfunction "1_1") (pintype "passive"))
    )
    (net (code "156") (name "Net-(IC20C-OUT)") (class "Default")
      (node (ref "C68") (pin "2") (pinfunction "2_2") (pintype "passive"))
      (node (ref "IC20") (pin "8") (pinfunction "OUT_8") (pintype "output"))
      (node (ref "R101") (pin "1") (pinfunction "E_1") (pintype "passive"))
      (node (ref "R78") (pin "2") (pinfunction "2_2") (pintype "passive"))
    )
    (net (code "157") (name "Net-(IC20D--IN)") (class "Default")
      (node (ref "C67") (pin "1") (pinfunction "1_1") (pintype "passive"))
      (node (ref "IC20") (pin "13") (pinfunction "-IN_13") (pintype "input"))
      (node (ref "IC21") (pin "4") (pinfunction "OUT_4") (pintype "output"))
      (node (ref "R79") (pin "1") (pinfunction "1_1") (pintype "passive"))
    )
    (net (code "158") (name "Net-(IC20D-OUT)") (class "Default")
      (node (ref "C67") (pin "2") (pinfunction "2_2") (pintype "passive"))
      (node (ref "IC20") (pin "14") (pinfunction "OUT_14") (pintype "output"))
      (node (ref "R79") (pin "2") (pinfunction "2_2") (pintype "passive"))
      (node (ref "R98") (pin "1") (pinfunction "E_1") (pintype "passive"))
    )
    (net (code "159") (name "Net-(IC21A-CTRL)") (class "Default")
      (node (ref "IC21") (pin "3") (pinfunction "CTRL_3") (pintype "input"))
      (node (ref "R32") (pin "2") (pinfunction "2_2") (pintype "passive"))
    )
    (net (code "160") (name "Net-(IC21A-IN)") (class "Default")
      (node (ref "IC21") (pin "2") (pinfunction "IN_2") (pintype "input"))
      (node (ref "R80") (pin "2") (pinfunction "2_2") (pintype "passive"))
      (node (ref "R81") (pin "2") (pinfunction "2_2") (pintype "passive"))
    )
    (net (code "161") (name "Net-(IC21B-CTRL)") (class "Default")
      (node (ref "IC21") (pin "6") (pinfunction "CTRL_6") (pintype "input"))
      (node (ref "R31") (pin "2") (pinfunction "2_2") (pintype "passive"))
    )
    (net (code "162") (name "Net-(IC21B-IN)") (class "Default")
      (node (ref "IC21") (pin "7") (pinfunction "IN_7") (pintype "input"))
      (node (ref "R82") (pin "2") (pinfunction "2_2") (pintype "passive"))
      (node (ref "R83") (pin "2") (pinfunction "2_2") (pintype "passive"))
    )
    (net (code "163") (name "Net-(IC21C-CTRL)") (class "Default")
      (node (ref "IC21") (pin "11") (pinfunction "CTRL_11") (pintype "input"))
      (node (ref "R34") (pin "2") (pinfunction "2_2") (pintype "passive"))
    )
    (net (code "164") (name "Net-(IC21C-IN)") (class "Default")
      (node (ref "IC21") (pin "10") (pinfunction "IN_10") (pintype "input"))
      (node (ref "R84") (pin "2") (pinfunction "2_2") (pintype "passive"))
      (node (ref "R85") (pin "2") (pinfunction "2_2") (pintype "passive"))
    )
    (net (code "165") (name "Net-(IC21D-CTRL)") (class "Default")
      (node (ref "IC21") (pin "14") (pinfunction "CTRL_14") (pintype "input"))
      (node (ref "R33") (pin "2") (pinfunction "2_2") (pintype "passive"))
    )
    (net (code "166") (name "Net-(IC21D-IN)") (class "Default")
      (node (ref "IC21") (pin "15") (pinfunction "IN_15") (pintype "input"))
      (node (ref "R86") (pin "2") (pinfunction "2_2") (pintype "passive"))
      (node (ref "R87") (pin "2") (pinfunction "2_2") (pintype "passive"))
    )
    (net (code "167") (name "Net-(K1B-P)") (class "Default")
      (node (ref "K1") (pin "1") (pinfunction "P_1") (pintype "passive"))
      (node (ref "PWR") (pin "2") (pinfunction "2_2") (pintype "passive"))
    )
    (net (code "168") (name "Net-(K1B-S)") (class "Default")
      (node (ref "K1") (pin "7") (pinfunction "S_7") (pintype "passive"))
      (node (ref "PWR") (pin "3") (pinfunction "3_3") (pintype "passive"))
    )
    (net (code "169") (name "Net-(R1-Pad1)") (class "Default")
      (node (ref "R1") (pin "1") (pinfunction "1_1") (pintype "passive"))
      (node (ref "USB") (pin "1") (pinfunction "1_1") (pintype "passive"))
    )
    (net (code "170") (name "Net-(R88-E)") (class "Default")
      (node (ref "R46") (pin "1") (pinfunction "1_1") (pintype "passive"))
      (node (ref "R88") (pin "1") (pinfunction "E_1") (pintype "passive"))
    )
    (net (code "171") (name "Net-(R89-E)") (class "Default")
      (node (ref "R50") (pin "1") (pinfunction "1_1") (pintype "passive"))
      (node (ref "R89") (pin "1") (pinfunction "E_1") (pintype "passive"))
    )
    (net (code "172") (name "Net-(R90-S)") (class "Default")
      (node (ref "BEARING") (pin "3") (pinfunction "3_3") (pintype "passive"))
      (node (ref "R90") (pin "2") (pinfunction "S_2") (pintype "passive"))
    )
    (net (code "173") (name "Net-(R91-S)") (class "Default")
      (node (ref "BEARING") (pin "2") (pinfunction "2_2") (pintype "passive"))
      (node (ref "R91") (pin "2") (pinfunction "S_2") (pintype "passive"))
    )
    (net (code "174") (name "Net-(R92-S)") (class "Default")
      (node (ref "BEARING") (pin "1") (pinfunction "1_1") (pintype "passive"))
      (node (ref "R92") (pin "2") (pinfunction "S_2") (pintype "passive"))
    )
    (net (code "175") (name "Net-(R93-S)") (class "Default")
      (node (ref "MX") (pin "1") (pinfunction "1_1") (pintype "passive"))
      (node (ref "R93") (pin "2") (pinfunction "S_2") (pintype "passive"))
    )
    (net (code "176") (name "Net-(R94-S)") (class "Default")
      (node (ref "MX") (pin "2") (pinfunction "2_2") (pintype "passive"))
      (node (ref "R94") (pin "2") (pinfunction "S_2") (pintype "passive"))
    )
    (net (code "177") (name "Net-(R95-S)") (class "Default")
      (node (ref "MX") (pin "3") (pinfunction "3_3") (pintype "passive"))
      (node (ref "R95") (pin "2") (pinfunction "S_2") (pintype "passive"))
    )
    (net (code "178") (name "Net-(R96-S)") (class "Default")
      (node (ref "MY") (pin "3") (pinfunction "3_3") (pintype "passive"))
      (node (ref "R96") (pin "2") (pinfunction "S_2") (pintype "passive"))
    )
    (net (code "179") (name "Net-(R97-S)") (class "Default")
      (node (ref "MY") (pin "2") (pinfunction "2_2") (pintype "passive"))
      (node (ref "R97") (pin "2") (pinfunction "S_2") (pintype "passive"))
    )
    (net (code "180") (name "Net-(R98-S)") (class "Default")
      (node (ref "MY") (pin "1") (pinfunction "1_1") (pintype "passive"))
      (node (ref "R98") (pin "2") (pinfunction "S_2") (pintype "passive"))
    )
    (net (code "181") (name "Net-(R99-S)") (class "Default")
      (node (ref "HEADING") (pin "1") (pinfunction "1_1") (pintype "passive"))
      (node (ref "R99") (pin "2") (pinfunction "S_2") (pintype "passive"))
    )
    (net (code "182") (name "Net-(R100-S)") (class "Default")
      (node (ref "HEADING") (pin "2") (pinfunction "2_2") (pintype "passive"))
      (node (ref "R100") (pin "2") (pinfunction "S_2") (pintype "passive"))
    )
    (net (code "183") (name "Net-(R101-S)") (class "Default")
      (node (ref "HEADING") (pin "3") (pinfunction "3_3") (pintype "passive"))
      (node (ref "R101") (pin "2") (pinfunction "S_2") (pintype "passive"))
    )
    (net (code "184") (name "Net-(R102-Pad1)") (class "Default")
      (node (ref "R102") (pin "1") (pinfunction "1_1") (pintype "passive"))
      (node (ref "R103") (pin "1") (pinfunction "1_1") (pintype "passive"))
      (node (ref "R43") (pin "1") (pinfunction "1_1") (pintype "passive"))
      (node (ref "R44") (pin "1") (pinfunction "1_1") (pintype "passive"))
    )
    (net (code "185") (name "Net-(R104-Pad1)") (class "Default")
      (node (ref "R104") (pin "1") (pinfunction "1_1") (pintype "passive"))
      (node (ref "R105") (pin "1") (pinfunction "1_1") (pintype "passive"))
      (node (ref "R47") (pin "1") (pinfunction "1_1") (pintype "passive"))
      (node (ref "R48") (pin "1") (pinfunction "1_1") (pintype "passive"))
    )
    (net (code "186") (name "SPI_CLK") (class "Default")
      (node (ref "IC1") (pin "34") (pinfunction "RB1/AN10/INT1/SCK/SCL_34") (pintype "bidirectional"))
      (node (ref "IC2") (pin "3") (pinfunction "SCK_3") (pintype "input"))
      (node (ref "IC3") (pin "3") (pinfunction "SCK_3") (pintype "input"))
      (node (ref "IC4") (pin "3") (pinfunction "SCK_3") (pintype "input"))
      (node (ref "IC5") (pin "3") (pinfunction "SCK_3") (pintype "input"))
      (node (ref "IC6") (pin "3") (pinfunction "SCK_3") (pintype "input"))
      (node (ref "IC7") (pin "3") (pinfunction "SCK_3") (pintype "input"))
    )
    (net (code "187") (name "SPI_DAT") (class "Default")
      (node (ref "IC1") (pin "26") (pinfunction "RC7/RX/DT/SDO_26") (pintype "bidirectional"))
      (node (ref "IC2") (pin "4") (pinfunction "SDI_4") (pintype "input"))
      (node (ref "IC3") (pin "4") (pinfunction "SDI_4") (pintype "input"))
      (node (ref "IC4") (pin "4") (pinfunction "SDI_4") (pintype "input"))
      (node (ref "IC5") (pin "4") (pinfunction "SDI_4") (pintype "input"))
      (node (ref "IC6") (pin "4") (pinfunction "SDI_4") (pintype "input"))
      (node (ref "IC7") (pin "4") (pinfunction "SDI_4") (pintype "input"))
    )
    (net (code "188") (name "USBDOA") (class "Default")
      (node (ref "IC1") (pin "2") (pinfunction "RA0/AN0_2") (pintype "bidirectional"))
      (node (ref "R3") (pin "1") (pinfunction "1_1") (pintype "passive"))
      (node (ref "U/D") (pin "2") (pinfunction "2_2") (pintype "passive"))
    )
    (net (code "189") (name "USB_DM") (class "Default")
      (node (ref "IC1") (pin "23") (pinfunction "RC4/D-/VM_23") (pintype "bidirectional"))
      (node (ref "USB") (pin "2") (pinfunction "2_2") (pintype "passive"))
    )
    (net (code "190") (name "USB_DP") (class "Default")
      (node (ref "IC1") (pin "24") (pinfunction "RC5/D+/VP_24") (pintype "bidirectional"))
      (node (ref "USB") (pin "3") (pinfunction "3_3") (pintype "passive"))
    )
    (net (code "191") (name "unconnected-(IC1-RB0{slash}AN12{slash}INT0{slash}LFT0{slash}SDI{slash}SDA-Pad33)") (class "Default")
      (node (ref "IC1") (pin "33") (pinfunction "RB0/AN12/INT0/LFT0/SDI/SDA_33") (pintype "bidirectional"))
    )
    (net (code "192") (name "unconnected-(IC17E-MODE-Pad1)") (class "Default")
      (node (ref "IC17") (pin "1") (pinfunction "MODE_1") (pintype "input"))
    )
    (net (code "193") (name "unconnected-(IC19E-MODE-Pad1)") (class "Default")
      (node (ref "IC19") (pin "1") (pinfunction "MODE_1") (pintype "input"))
    )
    (net (code "194") (name "unconnected-(IC21E-MODE-Pad1)") (class "Default")
      (node (ref "IC21") (pin "1") (pinfunction "MODE_1") (pintype "input"))
    )
  )
)
